# skyrizz_e32_se050.net
KiCad netlist of a schematic drawn in EasyEDA Pro
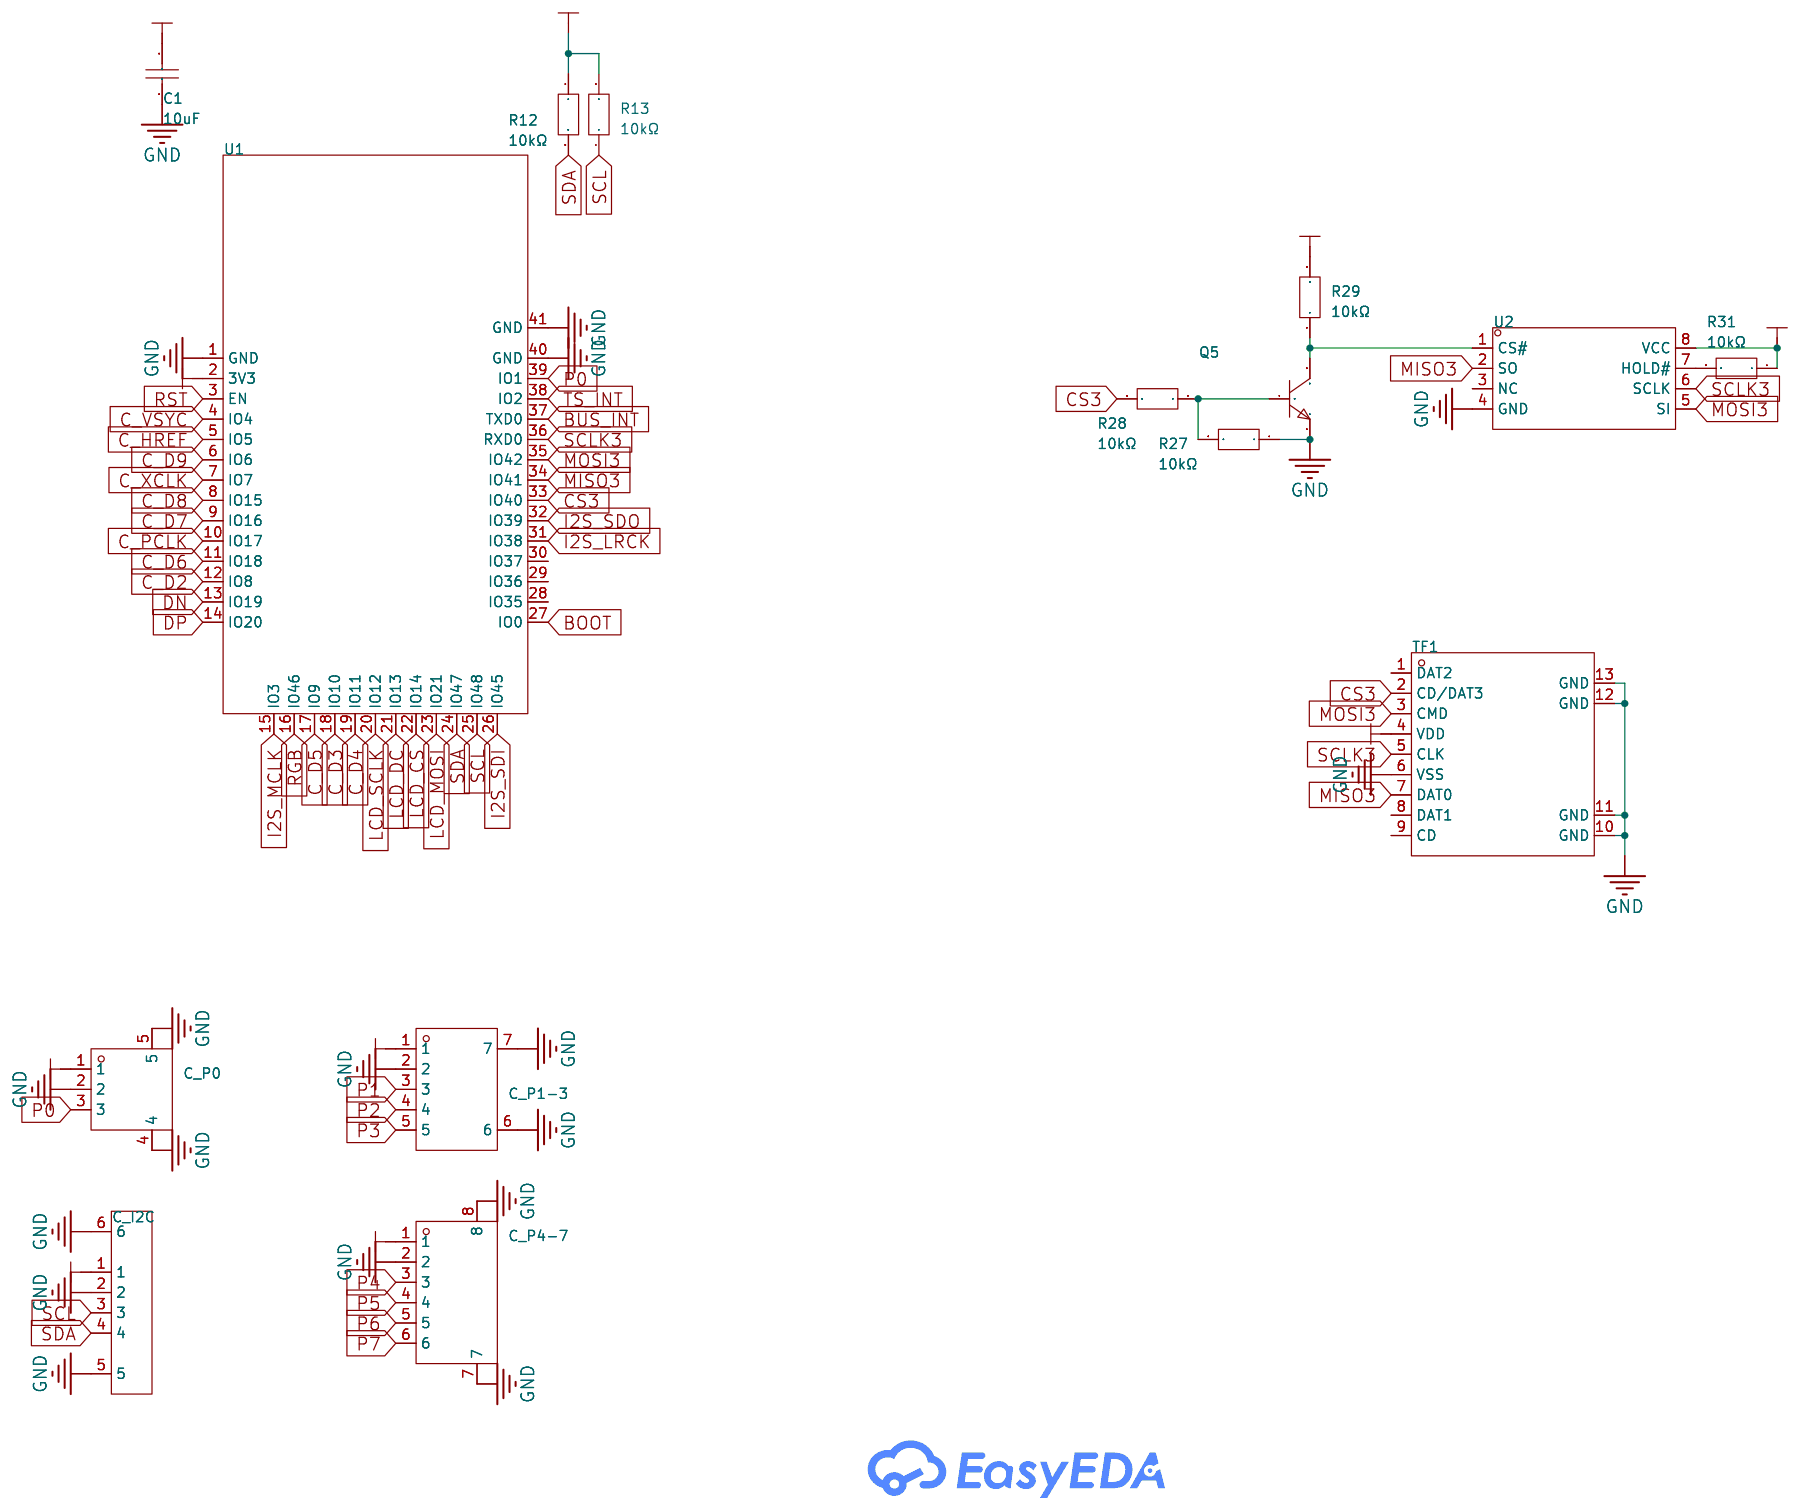
[diagram p0: MCU & MEMORY]
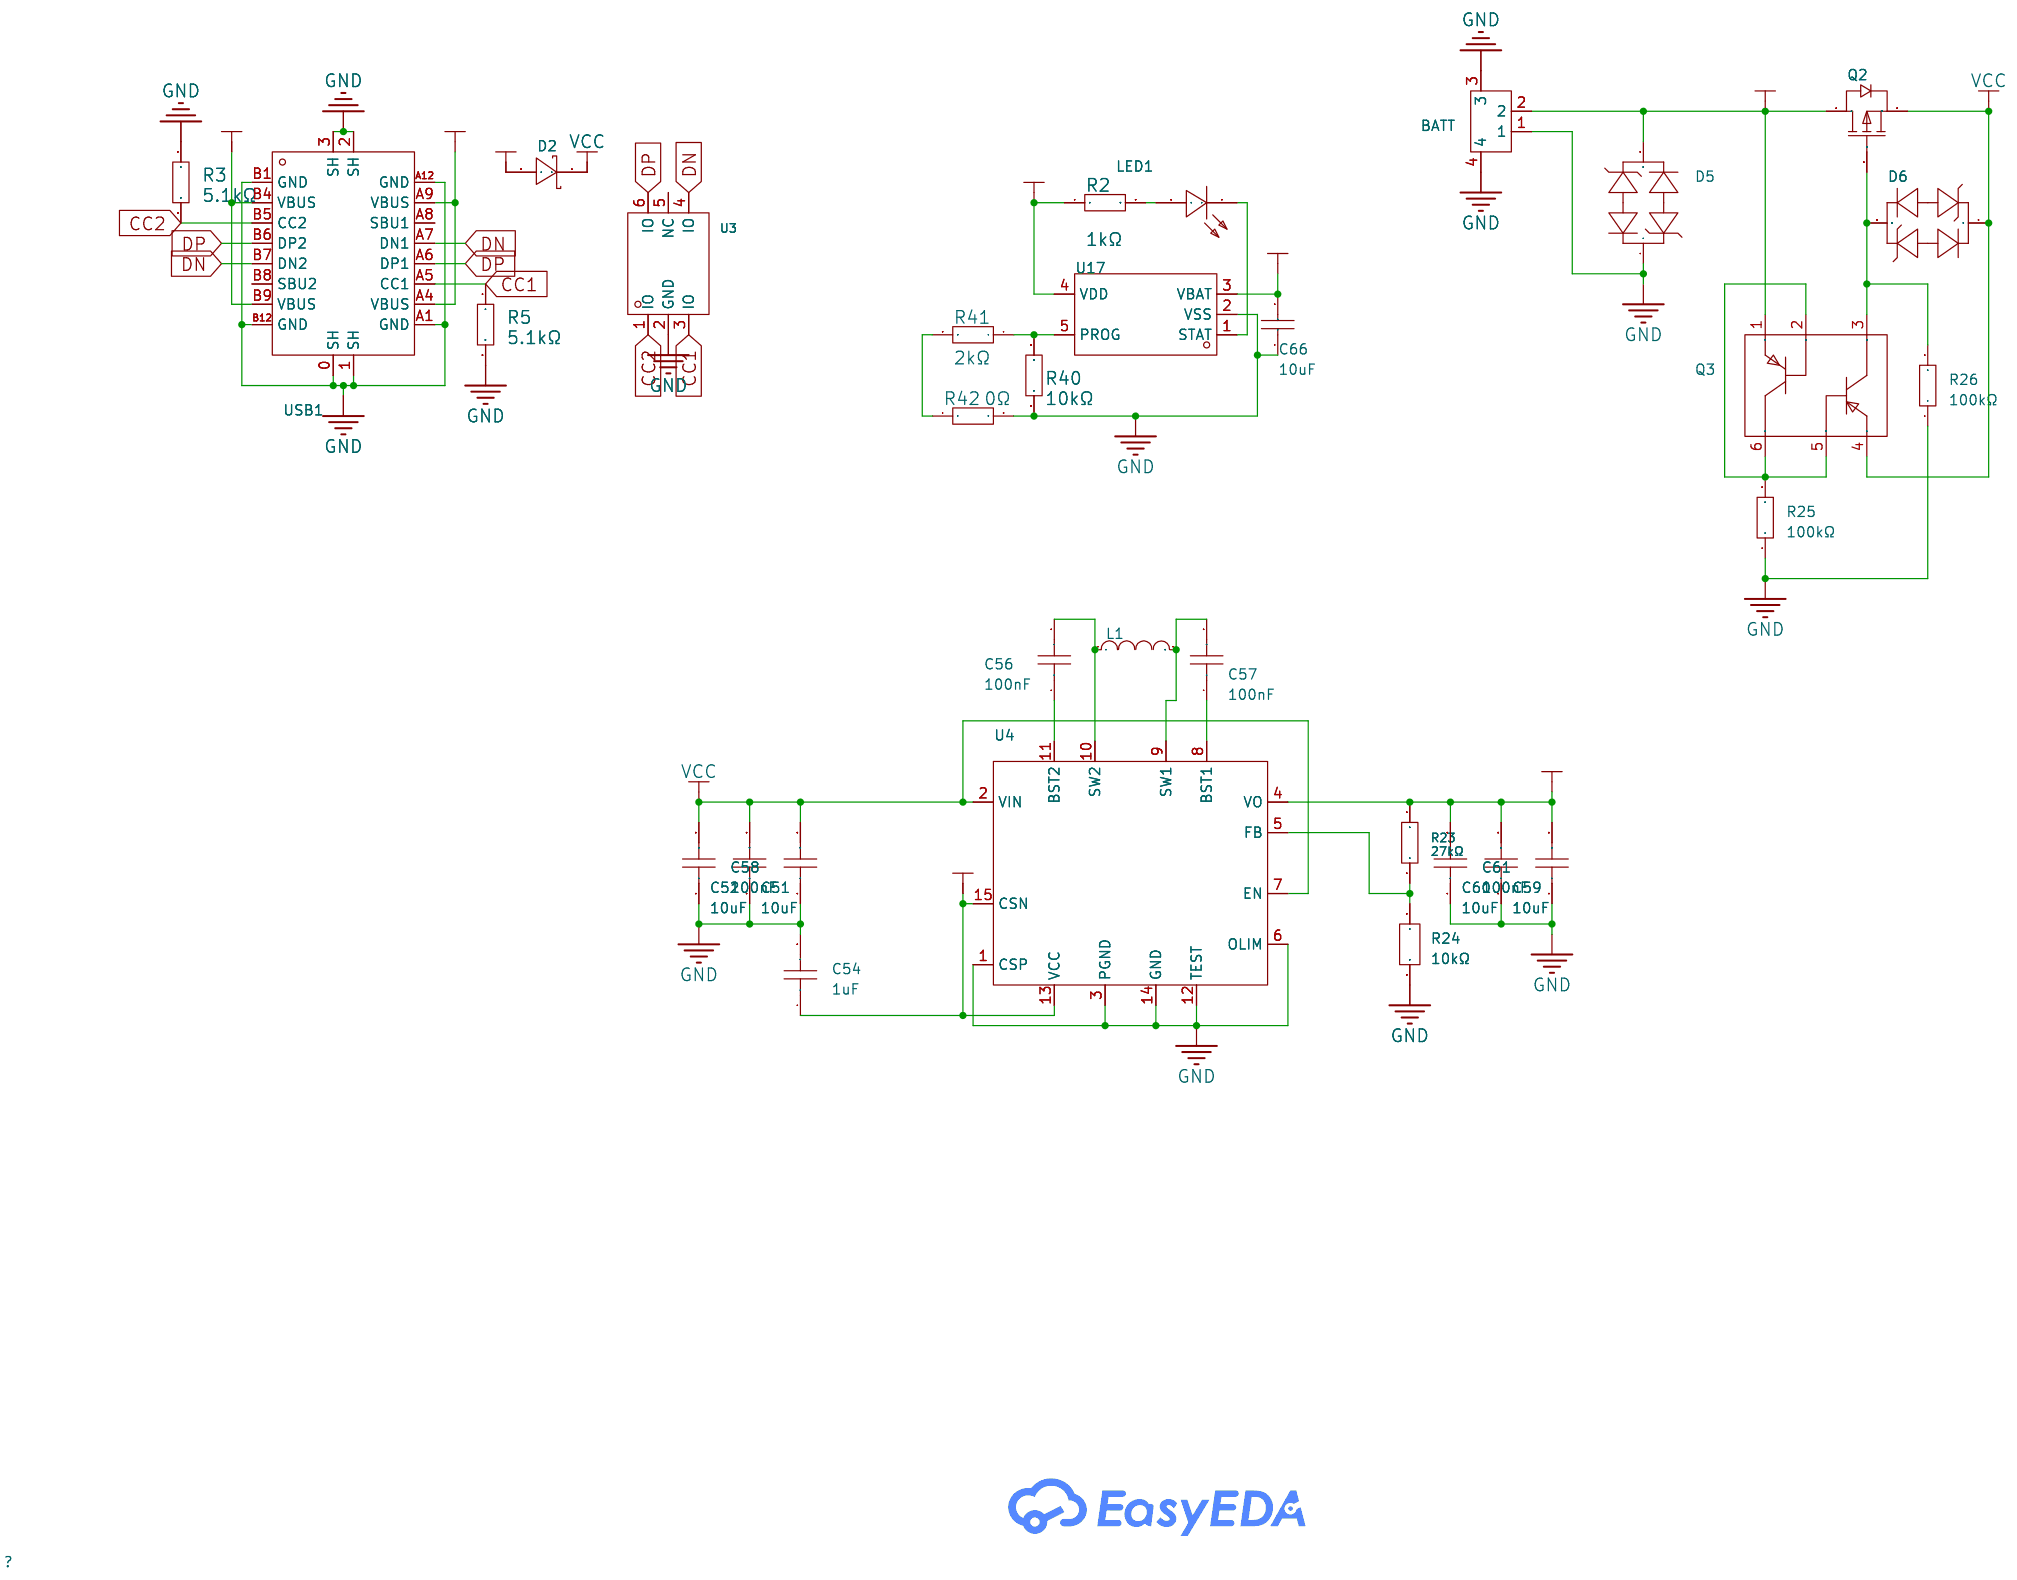
[diagram p1: POWER]
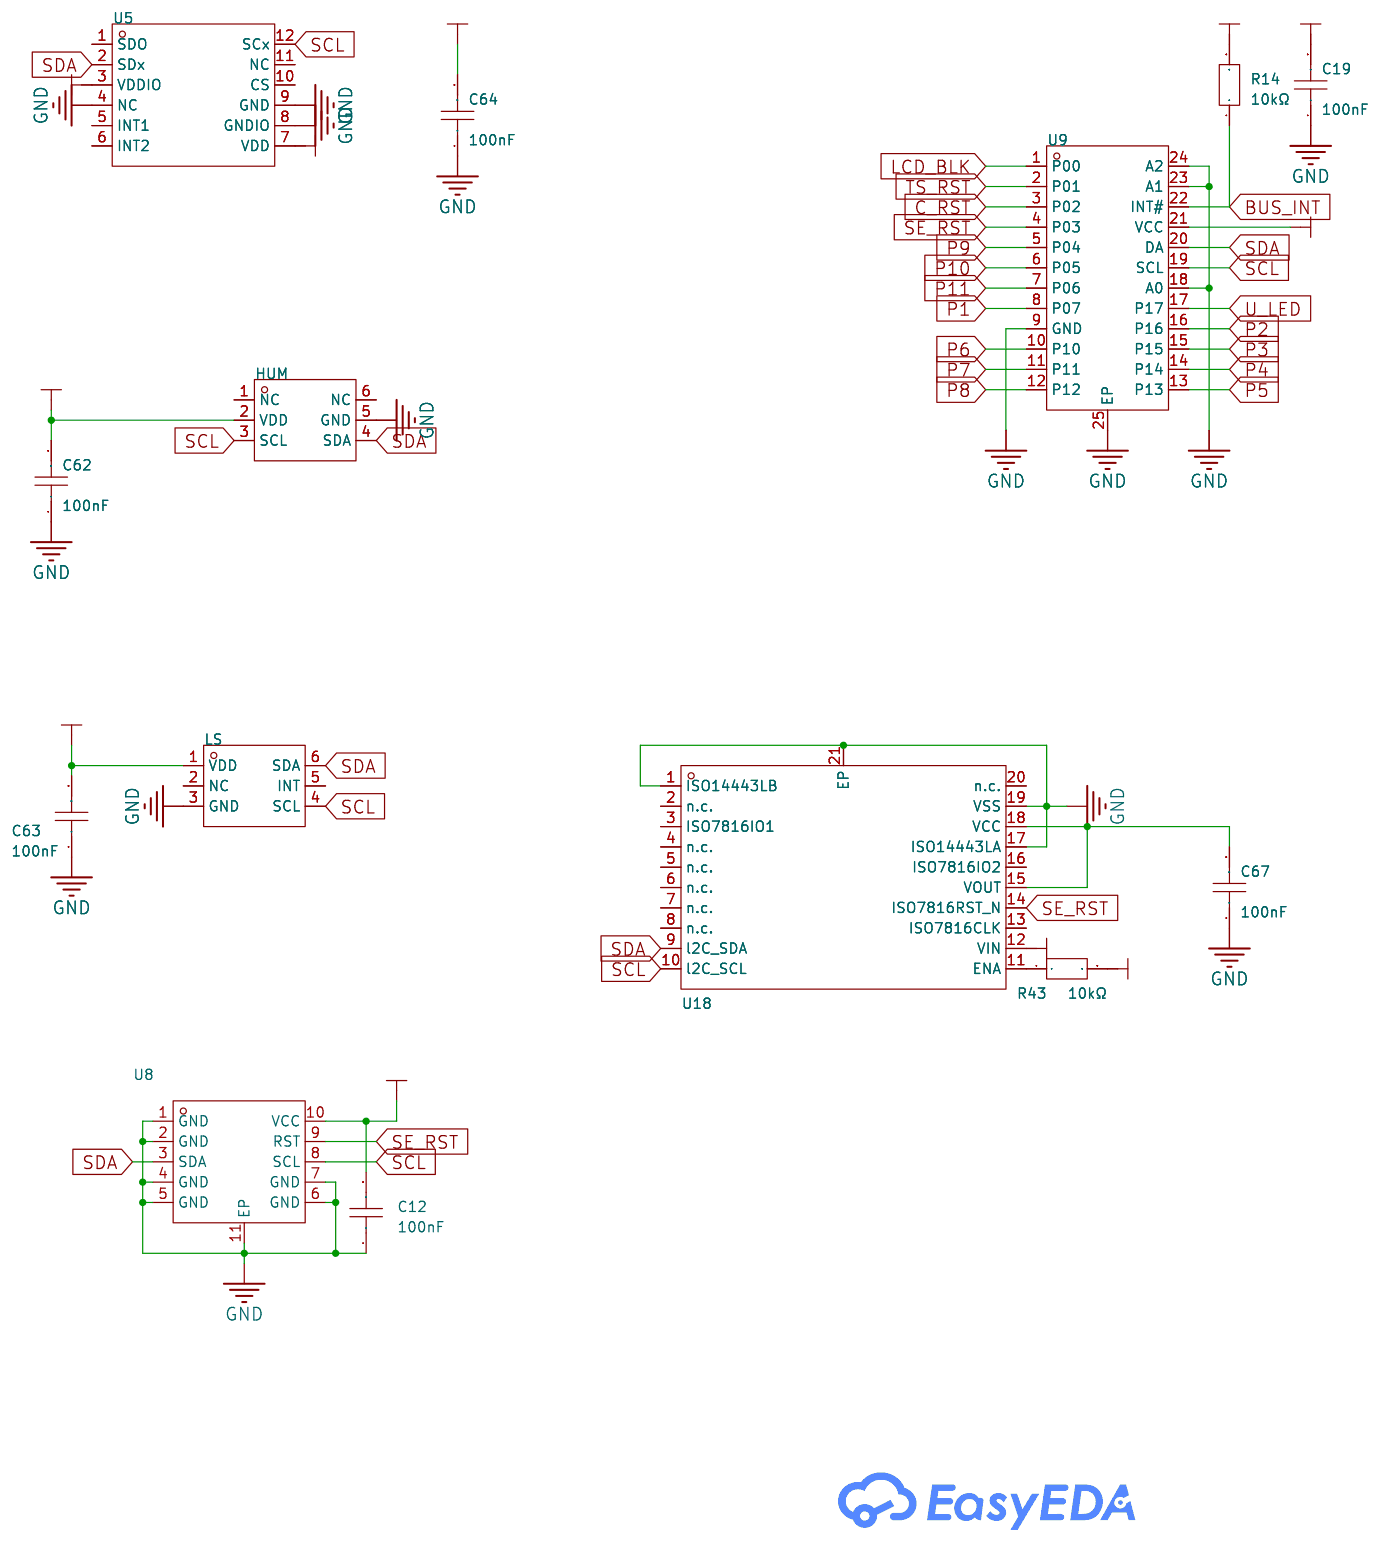
[diagram p2: SENSOR I2C]
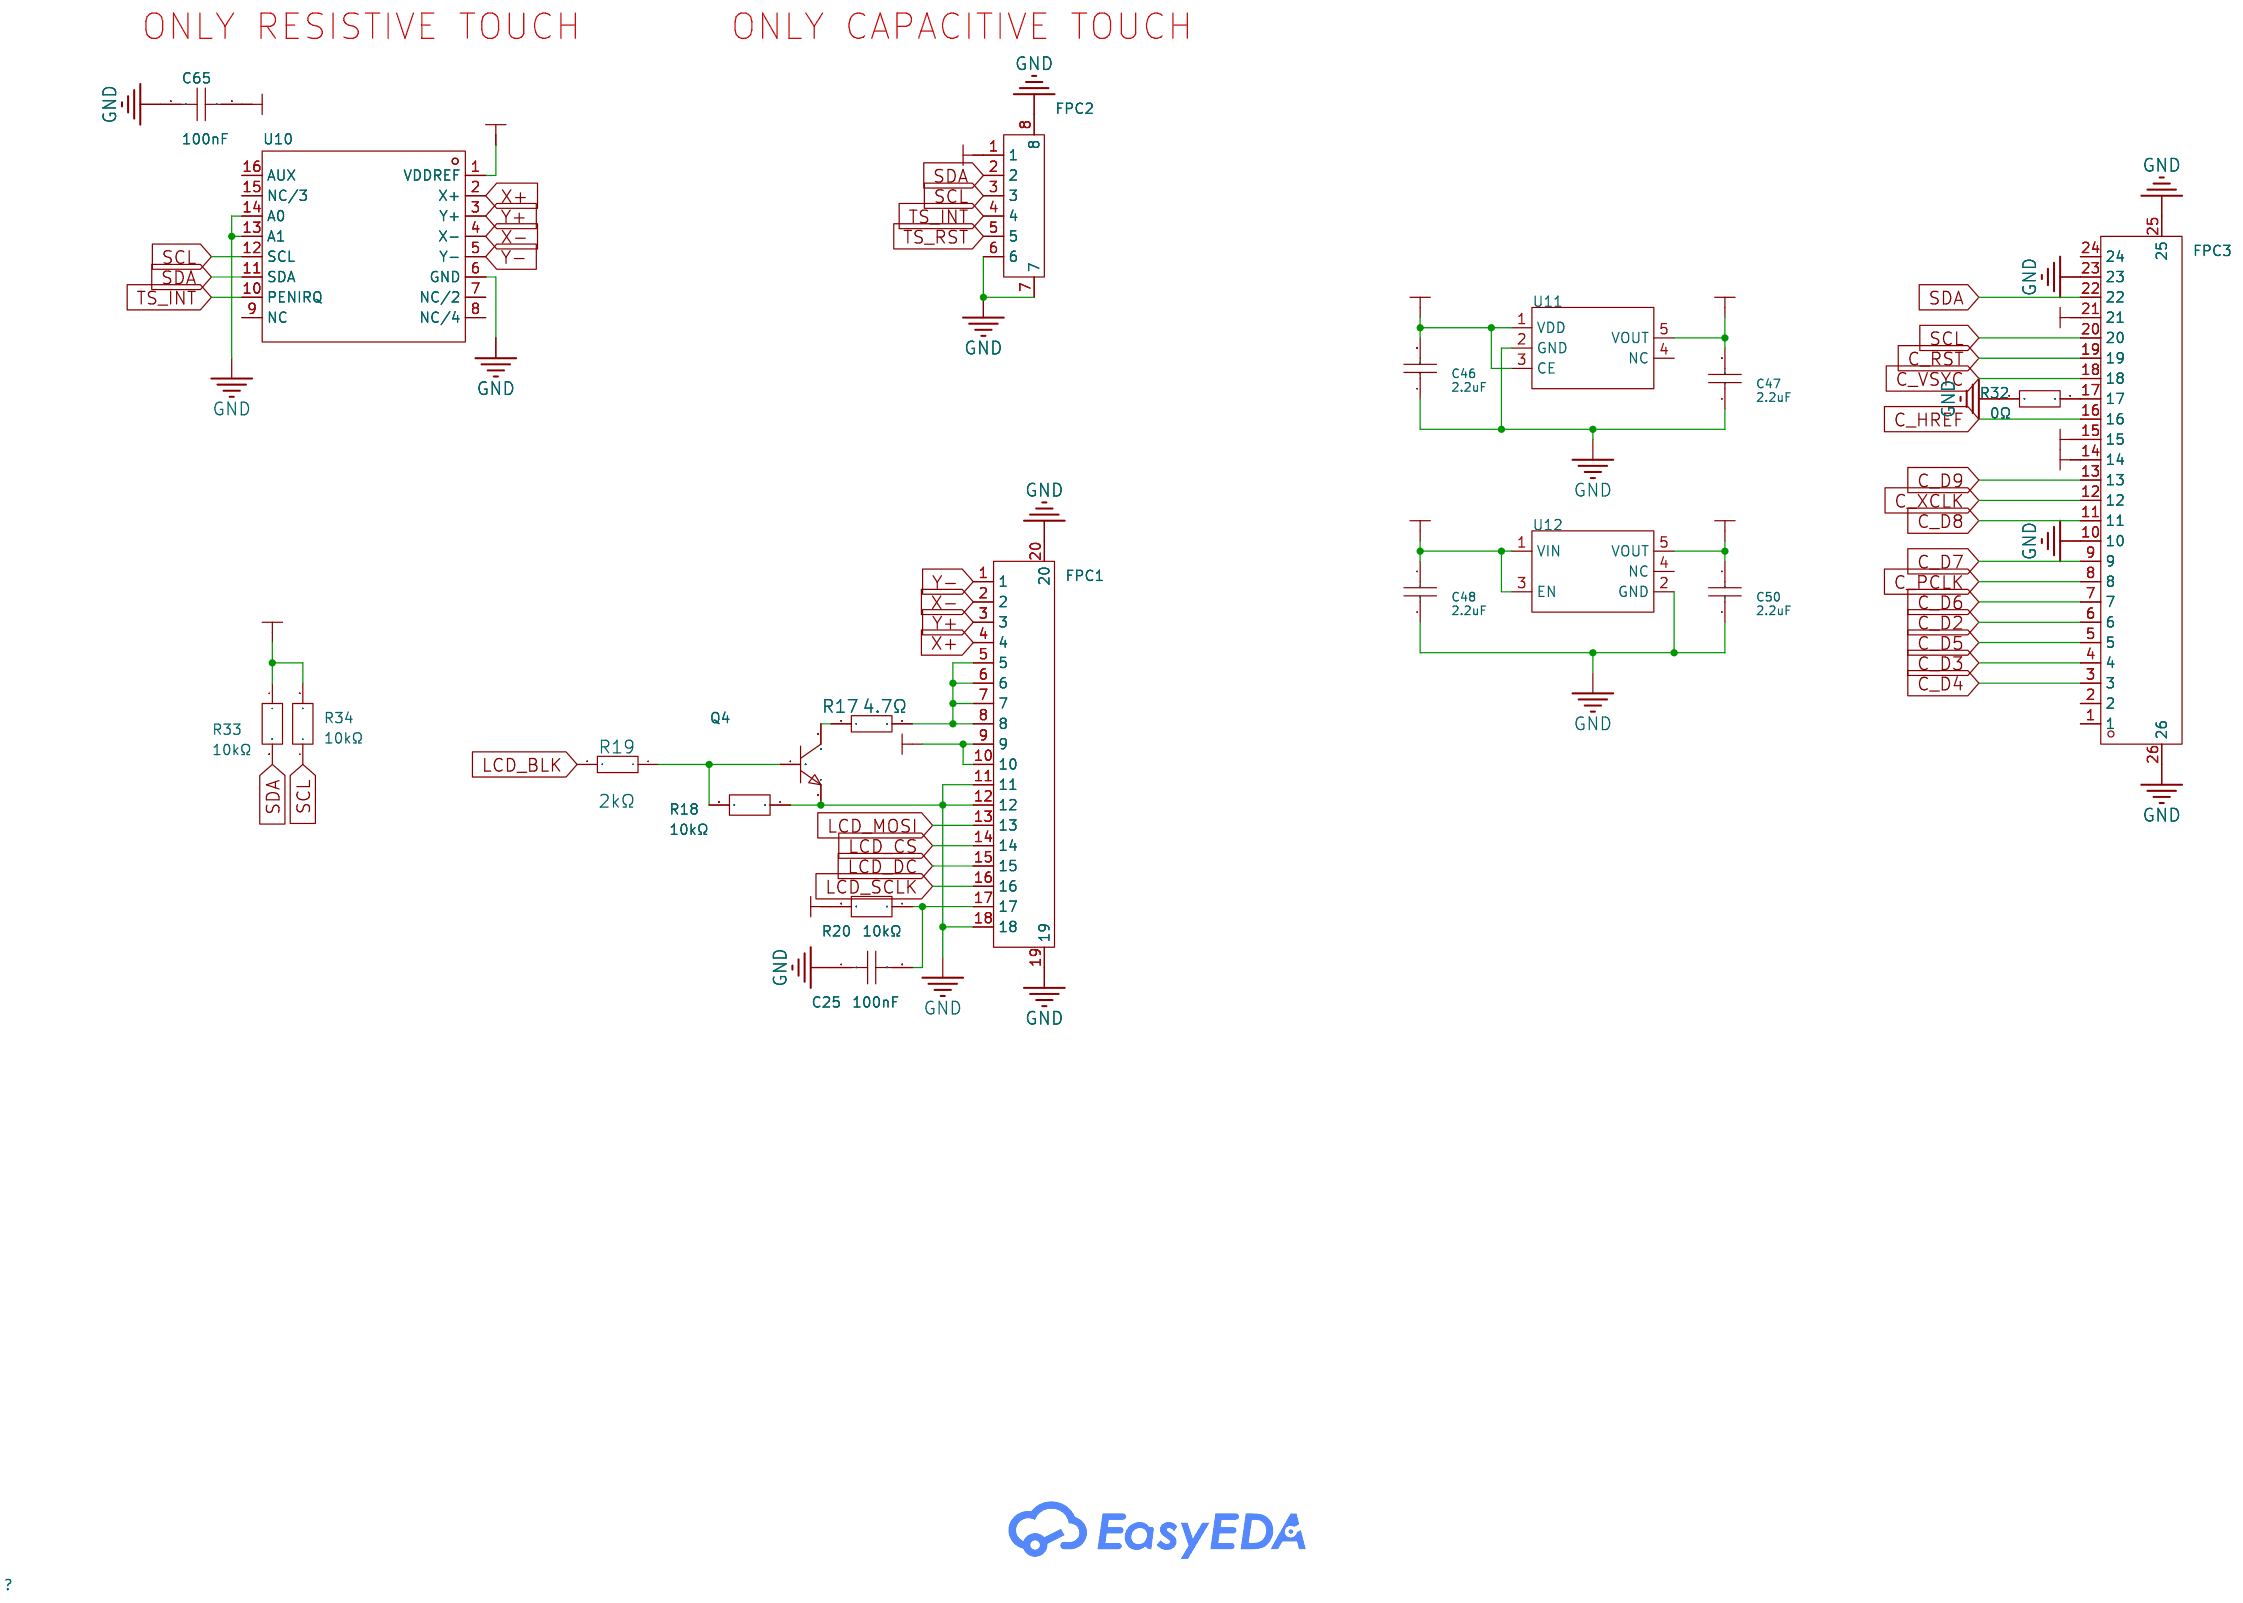
[diagram p3: LCD & CAM]
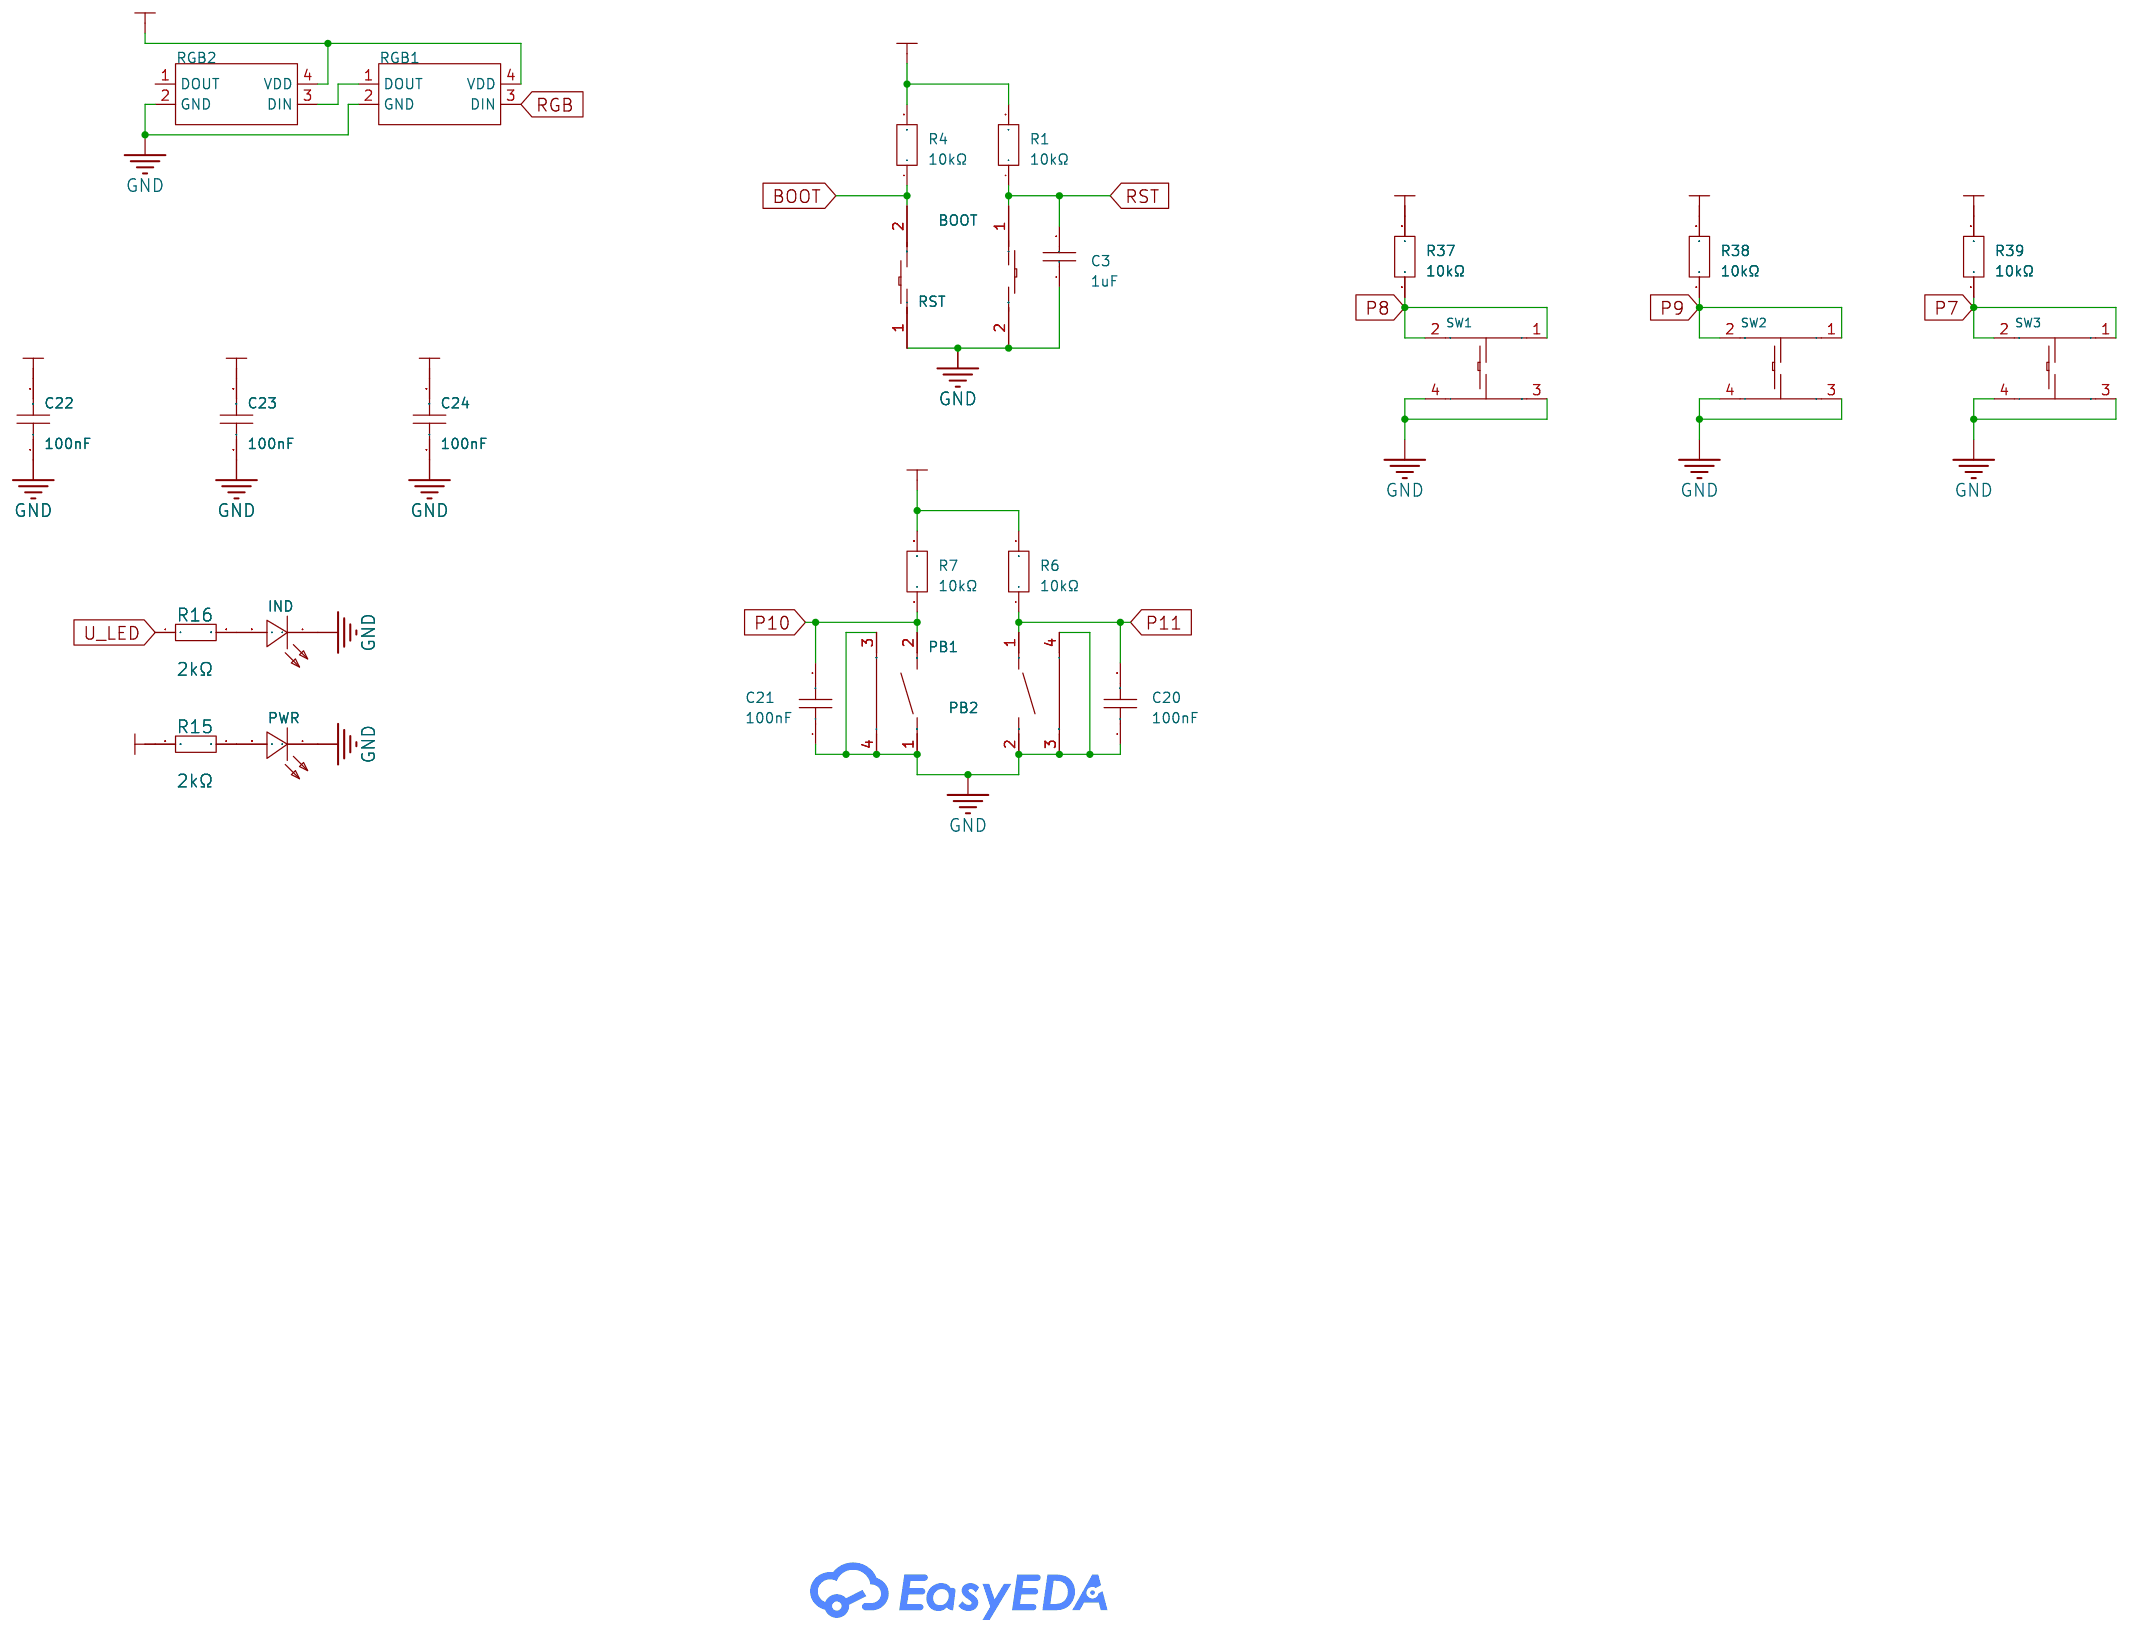
[diagram p4: BUTTON & IND]
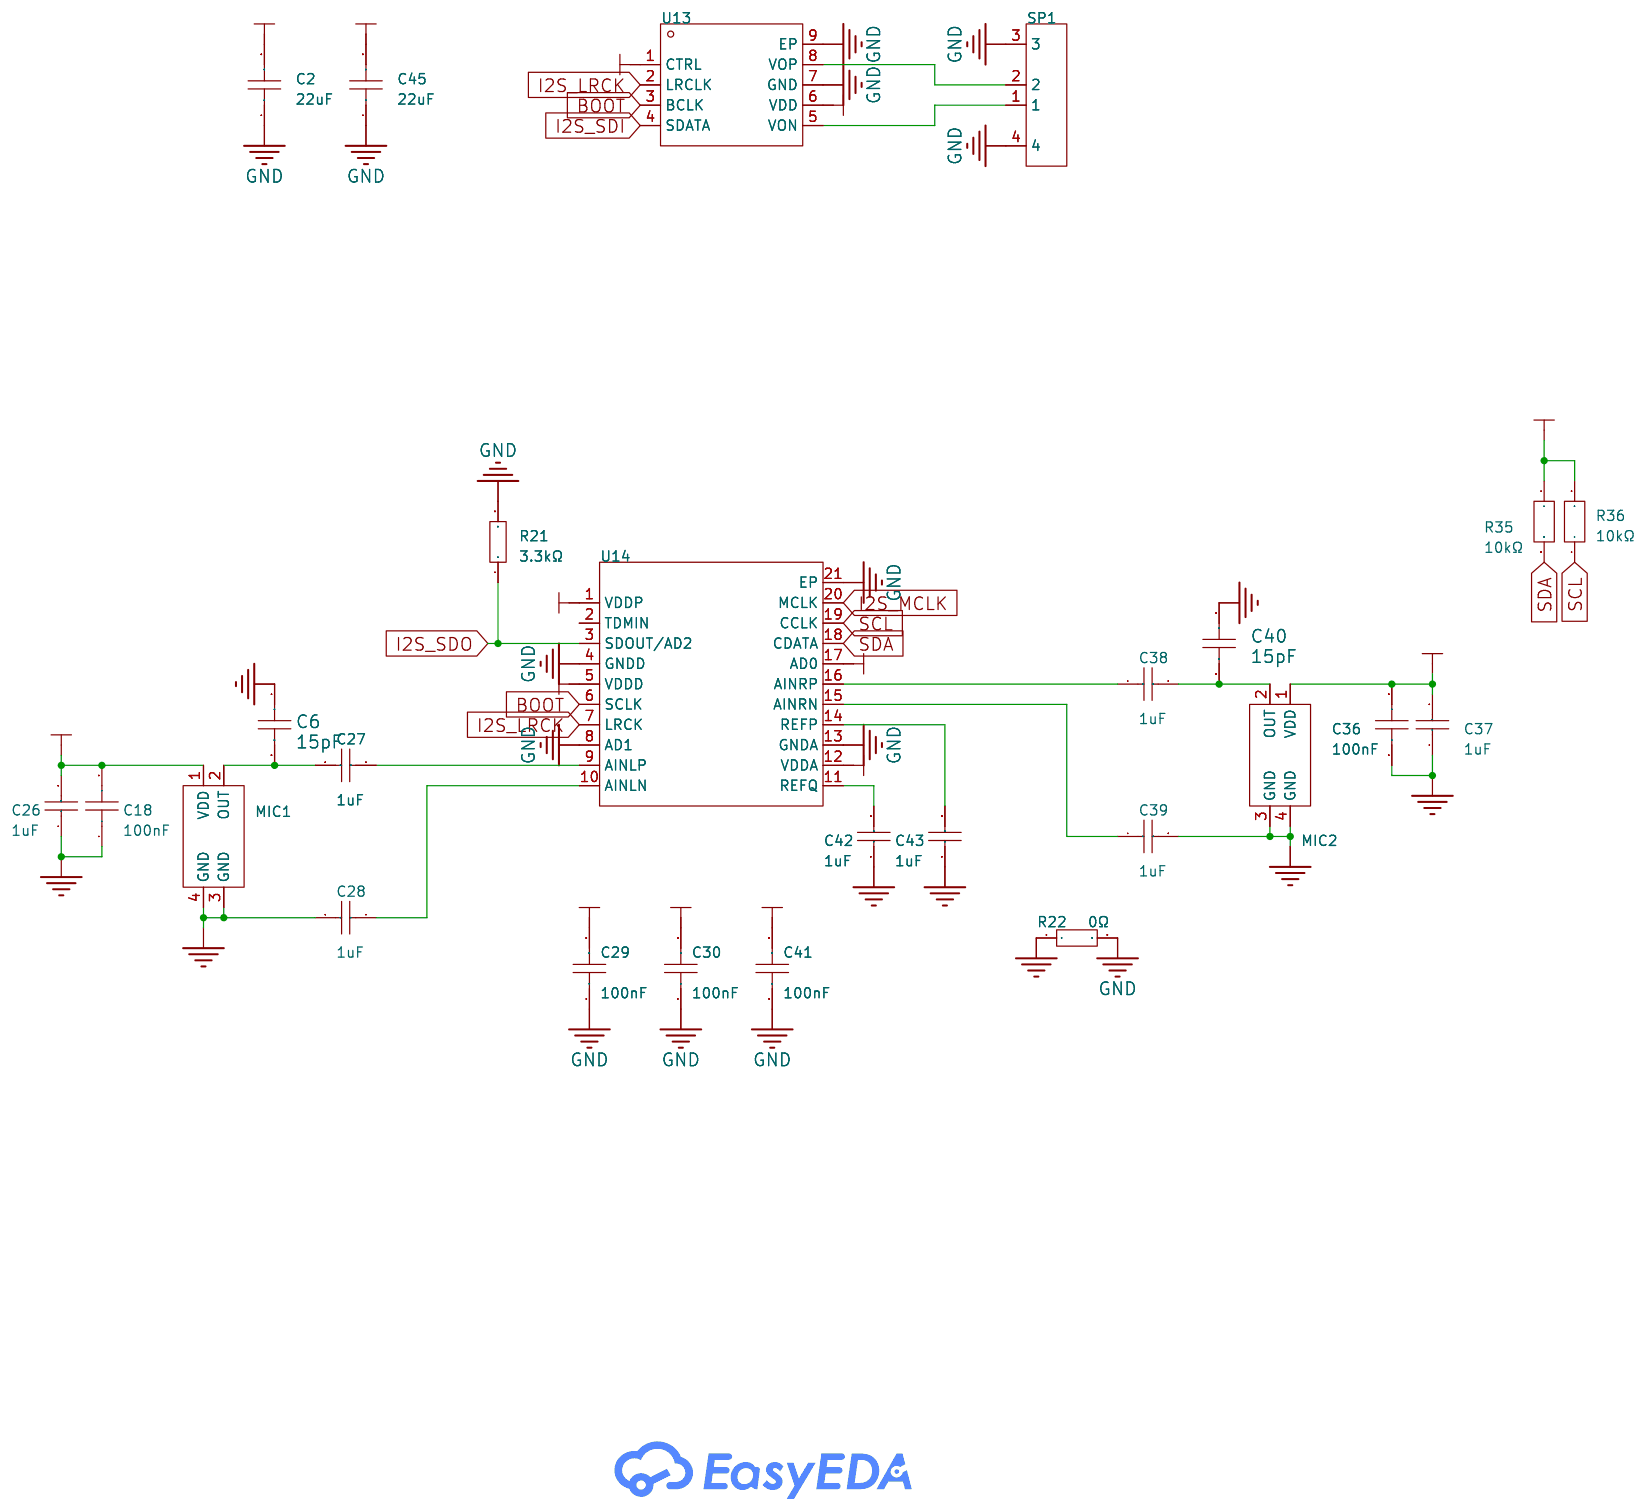
[diagram p5: MIC & SPEAKER]

(export (version "E")
  (design (tool "Eeschema 10.0.6"))
  (components
    (comp (ref "C1")
      (value "10uF")
      (description "Capacitance:10uF Tolerance:±20% Tolerance:±20% Voltage Rating:6.3V Temperature Coefficient:X5R")
      (fields
        (field (name "Manufacturer Part") "CL05A106MQ5NUNC")
        (field (name "Manufacturer") "SAMSUNG(三星)")
      )
      (libsource (lib "easyedapro") (part "CL05A106MQ5NUNC"))
    )
    (comp (ref "C_I2C")
      (value "SM04B-SRSS-TB(LF)(SN)")
      (footprint "easyedapro:CONN-SMD_4P-P1.00_SM04B-SRSS-TB-LF-SN")
      (fields (field (name "Manufacturer") "JST"))
      (libsource (lib "easyedapro") (part "SM04B-SRSS-TB (LF)(SN)"))
    )
    (comp (ref "C_P0")
      (value "SM03B-SRSS-TB(LF)(SN)")
      (footprint "easyedapro:CONN-SMD_SM03B-SRSS-TB-LF-SN-P")
      (fields (field (name "Manufacturer") "JST"))
      (libsource (lib "easyedapro") (part "SM03B-SRSS-TB(LF)(SN)(P)"))
    )
    (comp (ref "C_P1-3")
      (value "SM05B-SRSS-TB(LF)(SN)")
      (footprint "easyedapro:CONN-SMD_SM05B-SRSS-TB-LF-SN")
      (fields (field (name "Manufacturer") "JST"))
      (libsource (lib "easyedapro") (part "SM05B-SRSS-TB (LF)(SN)"))
    )
    (comp (ref "C_P4-7")
      (value "SM06B-SRSS-TB(LF)(SN)")
      (footprint "easyedapro:CONN-SMD_SM06B-SRSS-TB-LF-SN")
      (fields (field (name "Manufacturer") "JST"))
      (libsource (lib "easyedapro") (part "SM06B-SRSS-TB(LF)(SN)"))
    )
    (comp (ref "Q5")
      (value "MMBT3904")
      (footprint "easyedapro:SOT-23-3_L2.9-W1.3-P1.90-LS2.4-BR")
      (fields (field (name "Manufacturer") "DOWO(东沃)"))
      (libsource (lib "easyedapro") (part "MMBT3904_C22374713"))
    )
    (comp (ref "R12")
      (value "10kΩ")
      (footprint "easyedapro:R0201")
      (fields
        (field (name "Manufacturer Part") "0201WMF1002TEE")
        (field (name "Manufacturer") "UNI-ROYAL(厚声)")
      )
      (libsource (lib "easyedapro") (part "0201WMF1002TEE"))
    )
    (comp (ref "R13")
      (value "10kΩ")
      (footprint "easyedapro:R0201")
      (fields
        (field (name "Manufacturer Part") "0201WMF1002TEE")
        (field (name "Manufacturer") "UNI-ROYAL(厚声)")
      )
      (libsource (lib "easyedapro") (part "0201WMF1002TEE"))
    )
    (comp (ref "R27")
      (value "10kΩ")
      (footprint "easyedapro:R0201")
      (fields
        (field (name "Manufacturer Part") "0201WMF1002TEE")
        (field (name "Manufacturer") "UNI-ROYAL(厚声)")
      )
      (libsource (lib "easyedapro") (part "0201WMF1002TEE"))
    )
    (comp (ref "R28")
      (value "10kΩ")
      (footprint "easyedapro:R0201")
      (fields
        (field (name "Manufacturer Part") "0201WMF1002TEE")
        (field (name "Manufacturer") "UNI-ROYAL(厚声)")
      )
      (libsource (lib "easyedapro") (part "0201WMF1002TEE"))
    )
    (comp (ref "R29")
      (value "10kΩ")
      (footprint "easyedapro:R0201")
      (fields
        (field (name "Manufacturer Part") "0201WMF1002TEE")
        (field (name "Manufacturer") "UNI-ROYAL(厚声)")
      )
      (libsource (lib "easyedapro") (part "0201WMF1002TEE"))
    )
    (comp (ref "R31")
      (value "10kΩ")
      (footprint "easyedapro:R0201")
      (fields
        (field (name "Manufacturer Part") "0201WMF1002TEE")
        (field (name "Manufacturer") "UNI-ROYAL(厚声)")
      )
      (libsource (lib "easyedapro") (part "0201WMF1002TEE"))
    )
    (comp (ref "TF1")
      (value "TF-CARD H1.8")
      (footprint "easyedapro:TF-SMD_TF-CARD-H1.8")
      (fields (field (name "Manufacturer") "SHOU HAN(首韩)"))
      (libsource (lib "easyedapro") (part "TF-CARD H1.8"))
    )
    (comp (ref "U1")
      (value "ESP32-S3-WROOM-1-N16R8")
      (footprint "easyedapro:WIRELM-SMD_ESP32-S3-WROOM-1")
      (fields (field (name "Manufacturer") "ESPRESSIF(乐鑫)"))
      (libsource (lib "easyedapro") (part "ESP32-S3-WROOM-1(N16R8)"))
    )
    (comp (ref "U2")
      (value "GT30L24A3W")
      (footprint "easyedapro:SOIC-8_L5.3-W5.3-P1.27-LS8.0-BL")
      (fields (field (name "Manufacturer") "GENITOP(高通)"))
      (libsource (lib "easyedapro") (part "GT30L24A3W"))
    )
    (comp (ref "BATT")
      (value "PH-2P卧贴")
      (footprint "easyedapro:CONN-SMD_2P-P2.00_PH2.0-SPWB")
      (fields (field (name "Manufacturer") "BOOMELE(博穆精密)"))
      (libsource (lib "easyedapro") (part "PH2.0-2PWB"))
    )
    (comp (ref "C51")
      (value "10uF")
      (footprint "easyedapro:C0402")
      (description "Capacitance:10uF Tolerance:±20% Tolerance:±20% Voltage Rating:10V Temperature Coefficient:X5R")
      (fields
        (field (name "Manufacturer Part") "GRM155R61A106ME44D")
        (field (name "Manufacturer") "muRata(村田)")
      )
      (libsource (lib "easyedapro") (part "GRM155R61A106ME44D"))
    )
    (comp (ref "C52")
      (value "10uF")
      (footprint "easyedapro:C0402")
      (description "Capacitance:10uF Tolerance:±20% Tolerance:±20% Voltage Rating:10V Temperature Coefficient:X5R")
      (fields
        (field (name "Manufacturer Part") "GRM155R61A106ME44D")
        (field (name "Manufacturer") "muRata(村田)")
      )
      (libsource (lib "easyedapro") (part "GRM155R61A106ME44D"))
    )
    (comp (ref "C54")
      (value "1uF")
      (footprint "easyedapro:C0402")
      (description "Capacitance:1uF Tolerance:±10% Tolerance:±10% Voltage Rating:25V Temperature Coefficient:X5R")
      (fields
        (field (name "Manufacturer Part") "CL05A105KA5NQNC")
        (field (name "Manufacturer") "SAMSUNG(三星)")
      )
      (libsource (lib "easyedapro") (part "CL05A105KA5NQNC"))
    )
    (comp (ref "C56")
      (value "100nF")
      (footprint "easyedapro:C0402")
      (description "Capacitance:100nF Tolerance:±10% Tolerance:±10% Voltage Rating:16V Temperature Coefficient:X7R")
      (fields
        (field (name "Manufacturer Part") "CL05B104KO5NNNC")
        (field (name "Manufacturer") "SAMSUNG(三星)")
      )
      (libsource (lib "easyedapro") (part "CL05B104KO5NNNC"))
    )
    (comp (ref "C57")
      (value "100nF")
      (footprint "easyedapro:C0402")
      (description "Capacitance:100nF Tolerance:±10% Tolerance:±10% Voltage Rating:16V Temperature Coefficient:X7R")
      (fields
        (field (name "Manufacturer Part") "CL05B104KO5NNNC")
        (field (name "Manufacturer") "SAMSUNG(三星)")
      )
      (libsource (lib "easyedapro") (part "CL05B104KO5NNNC"))
    )
    (comp (ref "C58")
      (value "100nF")
      (footprint "easyedapro:C0402")
      (description "Capacitance:100nF Tolerance:±10% Tolerance:±10% Voltage Rating:16V Temperature Coefficient:X7R")
      (fields
        (field (name "Manufacturer Part") "CL05B104KO5NNNC")
        (field (name "Manufacturer") "SAMSUNG(三星)")
      )
      (libsource (lib "easyedapro") (part "CL05B104KO5NNNC"))
    )
    (comp (ref "C59")
      (value "10uF")
      (footprint "easyedapro:C0402")
      (description "Capacitance:10uF Tolerance:±20% Tolerance:±20% Voltage Rating:10V Temperature Coefficient:X5R")
      (fields
        (field (name "Manufacturer Part") "GRM155R61A106ME44D")
        (field (name "Manufacturer") "muRata(村田)")
      )
      (libsource (lib "easyedapro") (part "GRM155R61A106ME44D"))
    )
    (comp (ref "C60")
      (value "10uF")
      (footprint "easyedapro:C0402")
      (description "Capacitance:10uF Tolerance:±20% Tolerance:±20% Voltage Rating:10V Temperature Coefficient:X5R")
      (fields
        (field (name "Manufacturer Part") "GRM155R61A106ME44D")
        (field (name "Manufacturer") "muRata(村田)")
      )
      (libsource (lib "easyedapro") (part "GRM155R61A106ME44D"))
    )
    (comp (ref "C61")
      (value "100nF")
      (footprint "easyedapro:C0402")
      (description "Capacitance:100nF Tolerance:±10% Tolerance:±10% Voltage Rating:16V Temperature Coefficient:X7R")
      (fields
        (field (name "Manufacturer Part") "CL05B104KO5NNNC")
        (field (name "Manufacturer") "SAMSUNG(三星)")
      )
      (libsource (lib "easyedapro") (part "CL05B104KO5NNNC"))
    )
    (comp (ref "C66")
      (value "10uF")
      (description "Capacitance:10uF Tolerance:±20% Tolerance:±20% Voltage Rating:6.3V Temperature Coefficient:X5R")
      (fields
        (field (name "Manufacturer Part") "CL05A106MQ5NUNC")
        (field (name "Manufacturer") "SAMSUNG(三星)")
      )
      (libsource (lib "easyedapro") (part "CL05A106MQ5NUNC"))
    )
    (comp (ref "D2")
      (value "SS34")
      (footprint "easyedapro:SMA_L4.3-W2.6-LS5.2-RD")
      (fields (field (name "Manufacturer") "MDD(辰达半导体)"))
      (libsource (lib "easyedapro") (part "SS34_C8678"))
    )
    (comp (ref "D5")
      (value "PTVSUC3D5VB")
      (footprint "easyedapro:SOD-323_L1.8-W1.3-LS2.5-BI")
      (fields (field (name "Manufacturer") "Prisemi(芯导)"))
      (libsource (lib "easyedapro") (part "PTVSUC3D5VB"))
    )
    (comp (ref "D6")
      (value "PTVSUC3D5VB")
      (footprint "easyedapro:SOD-323_L1.8-W1.3-LS2.5-BI")
      (fields (field (name "Manufacturer") "Prisemi(芯导)"))
      (libsource (lib "easyedapro") (part "PTVSUC3D5VB"))
    )
    (comp (ref "L1")
      (value "2.2uH")
      (footprint "easyedapro:IND-SMD_L3.5-W3.0")
      (fields (field (name "Manufacturer Part") "SM3521-2R2MT") (field (name "Manufacturer") "SXN(顺翔诺)"))
      (libsource (lib "easyedapro") (part "SM3521-2R2MT"))
    )
    (comp (ref "LED1")
      (value "KT-0603R")
      (fields (field (name "Manufacturer") "KENTO"))
      (libsource (lib "easyedapro") (part "KT-0603R"))
    )
    (comp (ref "Q2")
      (value "AO3401A")
      (fields (field (name "Manufacturer") "AOS"))
      (libsource (lib "easyedapro") (part "AO3401A"))
    )
    (comp (ref "Q3")
      (value "BCM857BS")
      (footprint "easyedapro:SOT-363_L2.1-W1.3-P0.65-LS2.3-BL")
      (fields (field (name "Manufacturer") "FUXINSEMI(富芯森美)"))
      (libsource (lib "easyedapro") (part "BCM857BS"))
    )
    (comp (ref "R2")
      (value "1kΩ")
      (footprint "easyedapro:R0201")
      (fields
        (field (name "Manufacturer Part") "0201WMF1001TEE")
        (field (name "Manufacturer") "UNI-ROYAL(厚声)")
      )
      (libsource (lib "easyedapro") (part "0201WMF1001TEE"))
    )
    (comp (ref "R3")
      (value "5.1kΩ")
      (footprint "easyedapro:R0201")
      (fields
        (field (name "Manufacturer Part") "0201WMF5101TEE")
        (field (name "Manufacturer") "UNI-ROYAL(厚声)")
      )
      (libsource (lib "easyedapro") (part "0201WMF5101TEE"))
    )
    (comp (ref "R5")
      (value "5.1kΩ")
      (footprint "easyedapro:R0201")
      (fields
        (field (name "Manufacturer Part") "0201WMF5101TEE")
        (field (name "Manufacturer") "UNI-ROYAL(厚声)")
      )
      (libsource (lib "easyedapro") (part "0201WMF5101TEE"))
    )
    (comp (ref "R23")
      (value "27kΩ")
      (footprint "easyedapro:R0201")
      (fields
        (field (name "Manufacturer Part") "0201WMF2702TEE")
        (field (name "Manufacturer") "UNI-ROYAL(厚声)")
      )
      (libsource (lib "easyedapro") (part "0201WMF2702TEE"))
    )
    (comp (ref "R24")
      (value "10kΩ")
      (footprint "easyedapro:R0201")
      (fields
        (field (name "Manufacturer Part") "0201WMF1002TEE")
        (field (name "Manufacturer") "UNI-ROYAL(厚声)")
      )
      (libsource (lib "easyedapro") (part "0201WMF1002TEE"))
    )
    (comp (ref "R25")
      (value "100kΩ")
      (footprint "easyedapro:R0201")
      (fields
        (field (name "Manufacturer Part") "0201WMF1003TEE")
        (field (name "Manufacturer") "UNI-ROYAL(厚声)")
      )
      (libsource (lib "easyedapro") (part "0201WMF1003TEE"))
    )
    (comp (ref "R26")
      (value "100kΩ")
      (footprint "easyedapro:R0201")
      (fields
        (field (name "Manufacturer Part") "0201WMF1003TEE")
        (field (name "Manufacturer") "UNI-ROYAL(厚声)")
      )
      (libsource (lib "easyedapro") (part "0201WMF1003TEE"))
    )
    (comp (ref "R40")
      (value "10kΩ")
      (footprint "easyedapro:R0201")
      (fields
        (field (name "Manufacturer Part") "0201WMF1002TEE")
        (field (name "Manufacturer") "UNI-ROYAL(厚声)")
      )
      (libsource (lib "easyedapro") (part "0201WMF1001TEE"))
    )
    (comp (ref "R41")
      (value "2kΩ")
      (footprint "easyedapro:R0201")
      (fields
        (field (name "Manufacturer Part") "0201WMF2001TEE")
        (field (name "Manufacturer") "UNI-ROYAL(厚声)")
      )
      (libsource (lib "easyedapro") (part "0201WMF1001TEE"))
    )
    (comp (ref "R42")
      (value "0Ω")
      (footprint "easyedapro:R0402")
      (fields
        (field (name "Manufacturer Part") "0402WGF0000TCE")
        (field (name "Manufacturer") "UNI-ROYAL(厚声)")
      )
      (libsource (lib "easyedapro") (part "0402WGF0000TCE"))
    )
    (comp (ref "U3")
      (value "PUSB2X4Y")
      (footprint "easyedapro:SOT-363-6_L2.0-W1.3-P0.65-LS2.1-BL")
      (fields (field (name "Manufacturer") "TECH PUBLIC(台舟)"))
      (libsource (lib "easyedapro") (part "PUSB2X4Y"))
    )
    (comp (ref "U4")
      (value "JW3651QFNE#TRPBF")
      (footprint "easyedapro:QFN-15_L4.0-W3.0_JW3655E")
      (fields (field (name "Manufacturer") "Joulwatt(杰华特)"))
      (libsource (lib "easyedapro") (part "JW3651QFNE#TRPBF"))
    )
    (comp (ref "U17")
      (value "MCP73831T-2ACI/OT")
      (footprint "easyedapro:SOT-23-5_L3.0-W1.7-P0.95-LS2.8-BL")
      (fields (field (name "Manufacturer") "MICROCHIP(美国微芯)"))
      (libsource (lib "easyedapro") (part "MCP73831T-2ACI/OT"))
    )
    (comp (ref "USB1")
      (value "USB-TYPE-C-018")
      (footprint "easyedapro:USB-C_SMD-TYPE-C-31-M-12")
      (fields (field (name "Manufacturer") "DEALON(德艺隆)"))
      (libsource (lib "easyedapro") (part "USB-TYPE-C-018"))
    )
    (comp (ref "C12")
      (value "100nF")
      (footprint "easyedapro:C0201")
      (description "Capacitance:100nF Tolerance:±10% Tolerance:±10% Voltage Rating:10V Temperature Coefficient:X5R")
      (fields
        (field (name "Manufacturer Part") "CL03A104KP3NNNC")
        (field (name "Manufacturer") "SAMSUNG(三星)")
      )
      (libsource (lib "easyedapro") (part "CL03A104KP3NNNC"))
    )
    (comp (ref "C19")
      (value "100nF")
      (footprint "easyedapro:C0201")
      (description "Capacitance:100nF Tolerance:±10% Tolerance:±10% Voltage Rating:10V Temperature Coefficient:X5R")
      (fields
        (field (name "Manufacturer Part") "CL03A104KP3NNNC")
        (field (name "Manufacturer") "SAMSUNG(三星)")
      )
      (libsource (lib "easyedapro") (part "CL03A104KP3NNNC"))
    )
    (comp (ref "C62")
      (value "100nF")
      (footprint "easyedapro:C0201")
      (description "Capacitance:100nF Tolerance:±10% Tolerance:±10% Voltage Rating:10V Temperature Coefficient:X5R")
      (fields
        (field (name "Manufacturer Part") "CL03A104KP3NNNC")
        (field (name "Manufacturer") "SAMSUNG(三星)")
      )
      (libsource (lib "easyedapro") (part "CL03A104KP3NNNC"))
    )
    (comp (ref "C63")
      (value "100nF")
      (footprint "easyedapro:C0201")
      (description "Capacitance:100nF Tolerance:±10% Tolerance:±10% Voltage Rating:10V Temperature Coefficient:X5R")
      (fields
        (field (name "Manufacturer Part") "CL03A104KP3NNNC")
        (field (name "Manufacturer") "SAMSUNG(三星)")
      )
      (libsource (lib "easyedapro") (part "CL03A104KP3NNNC"))
    )
    (comp (ref "C64")
      (value "100nF")
      (footprint "easyedapro:C0201")
      (description "Capacitance:100nF Tolerance:±10% Tolerance:±10% Voltage Rating:10V Temperature Coefficient:X5R")
      (fields
        (field (name "Manufacturer Part") "CL03A104KP3NNNC")
        (field (name "Manufacturer") "SAMSUNG(三星)")
      )
      (libsource (lib "easyedapro") (part "CL03A104KP3NNNC"))
    )
    (comp (ref "C67")
      (value "100nF")
      (footprint "easyedapro:C0201")
      (description "Capacitance:100nF Tolerance:±10% Tolerance:±10% Voltage Rating:10V Temperature Coefficient:X5R")
      (fields
        (field (name "Manufacturer Part") "CL03A104KP3NNNC")
        (field (name "Manufacturer") "SAMSUNG(三星)")
      )
      (libsource (lib "easyedapro") (part "CL03A104KP3NNNC"))
    )
    (comp (ref "HUM")
      (value "AHT20")
      (footprint "easyedapro:SENSOR-SMD_L3.0-W3.0-P1.00-BR")
      (fields (field (name "Manufacturer") "广州奥松"))
      (libsource (lib "easyedapro") (part "AHT20_C2757850"))
    )
    (comp (ref "LS")
      (value "LTR-303ALS-01")
      (footprint "easyedapro:TDFN-6_L2.0-W2.0-P0.65-BL")
      (fields (field (name "Manufacturer") "LITEON(光宝)"))
      (libsource (lib "easyedapro") (part "LTR-303ALS-01"))
    )
    (comp (ref "R14")
      (value "10kΩ")
      (footprint "easyedapro:R0201")
      (fields
        (field (name "Manufacturer Part") "0201WMF1002TEE")
        (field (name "Manufacturer") "UNI-ROYAL(厚声)")
      )
      (libsource (lib "easyedapro") (part "0201WMF1002TEE"))
    )
    (comp (ref "R43")
      (value "10kΩ")
      (footprint "easyedapro:R0201")
      (fields
        (field (name "Manufacturer Part") "0201WMF1002TEE")
        (field (name "Manufacturer") "UNI-ROYAL(厚声)")
      )
      (libsource (lib "easyedapro") (part "0201WMF1002TEE"))
    )
    (comp (ref "U5")
      (value "SC7A20HTR")
      (footprint "easyedapro:LGA-12_L2.0-W2.0-P0.50-TL")
      (fields (field (name "Manufacturer") "SILAN(士兰微)"))
      (libsource (lib "easyedapro") (part "SC7A20HTR"))
    )
    (comp (ref "U8")
      (value "SLS32AIA020X2USON10")
      (footprint "easyedapro:USON-10_L3.0-W3.0-P0.50-BL-EP")
      (fields (field (name "Manufacturer") "Infineon(英飞凌)"))
      (libsource (lib "easyedapro") (part "SLS32AIA020X2USON10XTMA4"))
    )
    (comp (ref "U9")
      (value "XL9535QF24")
      (footprint "easyedapro:QFN-24_L4.0-W4.0-P0.50-BL-EP2.6")
      (fields (field (name "Manufacturer") "XINLUDA(信路达)"))
      (libsource (lib "easyedapro") (part "XL9535QF24"))
    )
    (comp (ref "U18")
      (value "SE050C2HQ1/Z01SDZ")
      (footprint "easyedapro:WQFN-20_L3.0-W3.0-P0.40-BL-EP1.7")
      (fields (field (name "Manufacturer") "NXP(恩智浦)"))
      (libsource (lib "easyedapro") (part "SE050C2HQ1/Z01SDZ"))
    )
    (comp (ref "C25")
      (value "100nF")
      (footprint "easyedapro:C0201")
      (description "Capacitance:100nF Tolerance:±10% Tolerance:±10% Voltage Rating:10V Temperature Coefficient:X5R")
      (fields
        (field (name "Manufacturer Part") "CL03A104KP3NNNC")
        (field (name "Manufacturer") "SAMSUNG(三星)")
      )
      (libsource (lib "easyedapro") (part "CL03A104KP3NNNC"))
    )
    (comp (ref "C46")
      (value "2.2uF")
      (footprint "easyedapro:C0201")
      (description "Capacitance:2.2uF Tolerance:±20% Tolerance:±20% Voltage Rating:6.3V Temperature Coefficient:X5R")
      (fields
        (field (name "Manufacturer Part") "GRM033R60J225ME47D")
        (field (name "Manufacturer") "muRata(村田)")
      )
      (libsource (lib "easyedapro") (part "GRM033R60J225ME47D"))
    )
    (comp (ref "C47")
      (value "2.2uF")
      (footprint "easyedapro:C0201")
      (description "Capacitance:2.2uF Tolerance:±20% Tolerance:±20% Voltage Rating:6.3V Temperature Coefficient:X5R")
      (fields
        (field (name "Manufacturer Part") "GRM033R60J225ME47D")
        (field (name "Manufacturer") "muRata(村田)")
      )
      (libsource (lib "easyedapro") (part "GRM033R60J225ME47D"))
    )
    (comp (ref "C48")
      (value "2.2uF")
      (footprint "easyedapro:C0201")
      (description "Capacitance:2.2uF Tolerance:±20% Tolerance:±20% Voltage Rating:6.3V Temperature Coefficient:X5R")
      (fields
        (field (name "Manufacturer Part") "GRM033R60J225ME47D")
        (field (name "Manufacturer") "muRata(村田)")
      )
      (libsource (lib "easyedapro") (part "GRM033R60J225ME47D"))
    )
    (comp (ref "C50")
      (value "2.2uF")
      (footprint "easyedapro:C0201")
      (description "Capacitance:2.2uF Tolerance:±20% Tolerance:±20% Voltage Rating:6.3V Temperature Coefficient:X5R")
      (fields
        (field (name "Manufacturer Part") "GRM033R60J225ME47D")
        (field (name "Manufacturer") "muRata(村田)")
      )
      (libsource (lib "easyedapro") (part "GRM033R60J225ME47D"))
    )
    (comp (ref "C65")
      (value "100nF")
      (footprint "easyedapro:C0201")
      (description "Capacitance:100nF Tolerance:±10% Tolerance:±10% Voltage Rating:10V Temperature Coefficient:X5R")
      (fields
        (field (name "Manufacturer Part") "CL03A104KP3NNNC")
        (field (name "Manufacturer") "SAMSUNG(三星)")
      )
      (libsource (lib "easyedapro") (part "CL03A104KP3NNNC"))
    )
    (comp (ref "FPC1")
      (value "FPC-0.5FX-18PWBH15")
      (footprint "easyedapro:FPC-SMD_18P-P0.50_XUNPU_FPC-0.5FX-18PWBH15")
      (fields (field (name "Manufacturer") "XUNPU(讯普)"))
      (libsource (lib "easyedapro") (part "FPC-0.5FX-18PWBH15"))
    )
    (comp (ref "FPC2")
      (value "FPC06-T1T1-2021-A")
      (footprint "easyedapro:FPC-SMD_FPC06-T1T1-2021-A")
      (fields (field (name "Manufacturer") "SHETIME(高钺达)"))
      (libsource (lib "easyedapro") (part "FPC06-T1T1-2021-A"))
    )
    (comp (ref "FPC3")
      (value "FPC-0.5FX-24PH20")
      (footprint "easyedapro:FPC-SMD_24P-P0.50_YUANDI_FPC-0.5FX-24PH20")
      (fields (field (name "Manufacturer") "Yuandi(元迪)"))
      (libsource (lib "easyedapro") (part "FPC-0.5FX-24PH20"))
    )
    (comp (ref "Q4")
      (value "MMBT3904")
      (footprint "easyedapro:SOT-23-3_L2.9-W1.3-P1.90-LS2.4-BR")
      (fields (field (name "Manufacturer") "DOWO(东沃)"))
      (libsource (lib "easyedapro") (part "MMBT3904_C22374713"))
    )
    (comp (ref "R17")
      (value "4.7Ω")
      (fields
        (field (name "Manufacturer Part") "0603WAF470KT5E")
        (field (name "Manufacturer") "UNI-ROYAL(厚声)")
      )
      (libsource (lib "easyedapro") (part "0603WAF470KT5E"))
    )
    (comp (ref "R18")
      (value "10kΩ")
      (footprint "easyedapro:R0201")
      (fields
        (field (name "Manufacturer Part") "0201WMF1002TEE")
        (field (name "Manufacturer") "UNI-ROYAL(厚声)")
      )
      (libsource (lib "easyedapro") (part "0201WMF1002TEE"))
    )
    (comp (ref "R19")
      (value "2kΩ")
      (footprint "easyedapro:R0201")
      (fields
        (field (name "Manufacturer Part") "0201WMF2001TEE")
        (field (name "Manufacturer") "UNI-ROYAL(厚声)")
      )
      (libsource (lib "easyedapro") (part "0201WMF2001TEE"))
    )
    (comp (ref "R20")
      (value "10kΩ")
      (footprint "easyedapro:R0201")
      (fields
        (field (name "Manufacturer Part") "0201WMF1002TEE")
        (field (name "Manufacturer") "UNI-ROYAL(厚声)")
      )
      (libsource (lib "easyedapro") (part "0201WMF1002TEE"))
    )
    (comp (ref "R32")
      (value "0Ω")
      (footprint "easyedapro:R0603")
      (fields
        (field (name "Manufacturer Part") "0603WAF0000T5E")
        (field (name "Manufacturer") "UNI-ROYAL(厚声)")
      )
      (libsource (lib "easyedapro") (part "0603WAF0000T5E"))
    )
    (comp (ref "R33")
      (value "10kΩ")
      (footprint "easyedapro:R0201")
      (fields
        (field (name "Manufacturer Part") "0201WMF1002TEE")
        (field (name "Manufacturer") "UNI-ROYAL(厚声)")
      )
      (libsource (lib "easyedapro") (part "0201WMF1002TEE"))
    )
    (comp (ref "R34")
      (value "10kΩ")
      (footprint "easyedapro:R0201")
      (fields
        (field (name "Manufacturer Part") "0201WMF1002TEE")
        (field (name "Manufacturer") "UNI-ROYAL(厚声)")
      )
      (libsource (lib "easyedapro") (part "0201WMF1002TEE"))
    )
    (comp (ref "U10")
      (value "TSC2007IPWR")
      (footprint "easyedapro:TSSOP-16_L5.0-W4.4-P0.65-LS6.4-BL")
      (fields (field (name "Manufacturer") "TI(德州仪器)"))
      (libsource (lib "easyedapro") (part "TSC2007IPWR"))
    )
    (comp (ref "U11")
      (value "BL8555-28PRA")
      (footprint "easyedapro:SOT-23-5_L3.0-W1.7-P0.95-LS2.8-BL")
      (fields (field (name "Manufacturer") "BL(上海贝岭)"))
      (libsource (lib "easyedapro") (part "BL8555-28PRA"))
    )
    (comp (ref "U12")
      (value "AP7343Q-18W5-7")
      (footprint "easyedapro:SOT-23-5_L3.0-W1.7-P0.95-LS2.8-BR")
      (fields (field (name "Manufacturer") "DIODES(美台)"))
      (libsource (lib "easyedapro") (part "AP7343Q-18W5-7_C3746471"))
    )
    (comp (ref "BOOT")
      (value "B3U-1000P")
      (footprint "easyedapro:KEY-SMD_B3U-1000PM")
      (fields (field (name "Manufacturer") "OMRON(欧姆龙)"))
      (libsource (lib "easyedapro") (part "B3U-1000P"))
    )
    (comp (ref "C3")
      (value "1uF")
      (footprint "easyedapro:C0201")
      (description "Capacitance:1uF Tolerance:±20% Tolerance:±20% Voltage Rating:6.3V Temperature Coefficient:X5R")
      (fields
        (field (name "Manufacturer Part") "CL03A105MQ3CSNH")
        (field (name "Manufacturer") "SAMSUNG(三星)")
      )
      (libsource (lib "easyedapro") (part "CL03A105MQ3CSNH"))
    )
    (comp (ref "C20")
      (value "100nF")
      (footprint "easyedapro:C0201")
      (description "Capacitance:100nF Tolerance:±10% Tolerance:±10% Voltage Rating:10V Temperature Coefficient:X5R")
      (fields
        (field (name "Manufacturer Part") "CL03A104KP3NNNC")
        (field (name "Manufacturer") "SAMSUNG(三星)")
      )
      (libsource (lib "easyedapro") (part "CL03A104KP3NNNC"))
    )
    (comp (ref "C21")
      (value "100nF")
      (footprint "easyedapro:C0201")
      (description "Capacitance:100nF Tolerance:±10% Tolerance:±10% Voltage Rating:10V Temperature Coefficient:X5R")
      (fields
        (field (name "Manufacturer Part") "CL03A104KP3NNNC")
        (field (name "Manufacturer") "SAMSUNG(三星)")
      )
      (libsource (lib "easyedapro") (part "CL03A104KP3NNNC"))
    )
    (comp (ref "C22")
      (value "100nF")
      (footprint "easyedapro:C0201")
      (description "Capacitance:100nF Tolerance:±10% Tolerance:±10% Voltage Rating:10V Temperature Coefficient:X5R")
      (fields
        (field (name "Manufacturer Part") "CL03A104KP3NNNC")
        (field (name "Manufacturer") "SAMSUNG(三星)")
      )
      (libsource (lib "easyedapro") (part "CL03A104KP3NNNC"))
    )
    (comp (ref "C23")
      (value "100nF")
      (footprint "easyedapro:C0201")
      (description "Capacitance:100nF Tolerance:±10% Tolerance:±10% Voltage Rating:10V Temperature Coefficient:X5R")
      (fields
        (field (name "Manufacturer Part") "CL03A104KP3NNNC")
        (field (name "Manufacturer") "SAMSUNG(三星)")
      )
      (libsource (lib "easyedapro") (part "CL03A104KP3NNNC"))
    )
    (comp (ref "C24")
      (value "100nF")
      (footprint "easyedapro:C0201")
      (description "Capacitance:100nF Tolerance:±10% Tolerance:±10% Voltage Rating:10V Temperature Coefficient:X5R")
      (fields
        (field (name "Manufacturer Part") "CL03A104KP3NNNC")
        (field (name "Manufacturer") "SAMSUNG(三星)")
      )
      (libsource (lib "easyedapro") (part "CL03A104KP3NNNC"))
    )
    (comp (ref "IND")
      (value "KT-0603YG")
      (footprint "easyedapro:LED0603-RD")
      (fields (field (name "Manufacturer") "KENTO"))
      (libsource (lib "easyedapro") (part "XL-0603QYGC"))
    )
    (comp (ref "PB1")
      (value "TS24CA")
      (footprint "easyedapro:SW-SMD_2P-TS24CA")
      (fields (field (name "Manufacturer") "SHOU HAN(首韩)"))
      (libsource (lib "easyedapro") (part "TS24CA"))
    )
    (comp (ref "PB2")
      (value "TS24CA")
      (footprint "easyedapro:SW-SMD_2P-TS24CA")
      (fields (field (name "Manufacturer") "SHOU HAN(首韩)"))
      (libsource (lib "easyedapro") (part "TS24CA"))
    )
    (comp (ref "PWR")
      (value "KT-0603R")
      (fields (field (name "Manufacturer") "KENTO"))
      (libsource (lib "easyedapro") (part "KT-0603R"))
    )
    (comp (ref "R1")
      (value "10kΩ")
      (footprint "easyedapro:R0201")
      (fields
        (field (name "Manufacturer Part") "0201WMF1002TEE")
        (field (name "Manufacturer") "UNI-ROYAL(厚声)")
      )
      (libsource (lib "easyedapro") (part "0201WMF1002TEE"))
    )
    (comp (ref "R4")
      (value "10kΩ")
      (footprint "easyedapro:R0201")
      (fields
        (field (name "Manufacturer Part") "0201WMF1002TEE")
        (field (name "Manufacturer") "UNI-ROYAL(厚声)")
      )
      (libsource (lib "easyedapro") (part "0201WMF1002TEE"))
    )
    (comp (ref "R6")
      (value "10kΩ")
      (footprint "easyedapro:R0201")
      (fields
        (field (name "Manufacturer Part") "0201WMF1002TEE")
        (field (name "Manufacturer") "UNI-ROYAL(厚声)")
      )
      (libsource (lib "easyedapro") (part "0201WMF1002TEE"))
    )
    (comp (ref "R7")
      (value "10kΩ")
      (footprint "easyedapro:R0201")
      (fields
        (field (name "Manufacturer Part") "0201WMF1002TEE")
        (field (name "Manufacturer") "UNI-ROYAL(厚声)")
      )
      (libsource (lib "easyedapro") (part "0201WMF1002TEE"))
    )
    (comp (ref "R15")
      (value "2kΩ")
      (footprint "easyedapro:R0201")
      (fields
        (field (name "Manufacturer Part") "0201WMF2001TEE")
        (field (name "Manufacturer") "UNI-ROYAL(厚声)")
      )
      (libsource (lib "easyedapro") (part "0201WMF2001TEE"))
    )
    (comp (ref "R16")
      (value "2kΩ")
      (footprint "easyedapro:R0201")
      (fields
        (field (name "Manufacturer Part") "0201WMF2001TEE")
        (field (name "Manufacturer") "UNI-ROYAL(厚声)")
      )
      (libsource (lib "easyedapro") (part "0201WMF2001TEE"))
    )
    (comp (ref "R37")
      (value "10kΩ")
      (footprint "easyedapro:R0201")
      (fields
        (field (name "Manufacturer Part") "0201WMF1002TEE")
        (field (name "Manufacturer") "UNI-ROYAL(厚声)")
      )
      (libsource (lib "easyedapro") (part "0201WMF1002TEE"))
    )
    (comp (ref "R38")
      (value "10kΩ")
      (footprint "easyedapro:R0201")
      (fields
        (field (name "Manufacturer Part") "0201WMF1002TEE")
        (field (name "Manufacturer") "UNI-ROYAL(厚声)")
      )
      (libsource (lib "easyedapro") (part "0201WMF1002TEE"))
    )
    (comp (ref "R39")
      (value "10kΩ")
      (footprint "easyedapro:R0201")
      (fields
        (field (name "Manufacturer Part") "0201WMF1002TEE")
        (field (name "Manufacturer") "UNI-ROYAL(厚声)")
      )
      (libsource (lib "easyedapro") (part "0201WMF1002TEE"))
    )
    (comp (ref "RGB1")
      (value "XL-0807RGBC-2812B")
      (footprint "easyedapro:LED-SMD_4P-L2.0-W1.8_XL-0807RGBC-WS2812B")
      (fields (field (name "Manufacturer") "XINGLIGHT(成兴光)"))
      (libsource (lib "easyedapro") (part "XL-0807RGBC-WS2812B"))
    )
    (comp (ref "RGB2")
      (value "XL-0807RGBC-2812B")
      (footprint "easyedapro:LED-SMD_4P-L2.0-W1.8_XL-0807RGBC-WS2812B")
      (fields (field (name "Manufacturer") "XINGLIGHT(成兴光)"))
      (libsource (lib "easyedapro") (part "XL-0807RGBC-WS2812B"))
    )
    (comp (ref "RST")
      (value "B3U-1000P")
      (footprint "easyedapro:KEY-SMD_B3U-1000PM")
      (fields (field (name "Manufacturer") "OMRON(欧姆龙)"))
      (libsource (lib "easyedapro") (part "B3U-1000P"))
    )
    (comp (ref "SW1")
      (value "EVQQ2B03W")
      (footprint "easyedapro:KEY-SMD_4P-L6.5-W6.0-P4.0-LS6.6")
      (fields (field (name "Manufacturer") "PANASONIC(松下)"))
      (libsource (lib "easyedapro") (part "EVQQ2B03W"))
    )
    (comp (ref "SW2")
      (value "EVQQ2B03W")
      (footprint "easyedapro:KEY-SMD_4P-L6.5-W6.0-P4.0-LS6.6")
      (fields (field (name "Manufacturer") "PANASONIC(松下)"))
      (libsource (lib "easyedapro") (part "EVQQ2B03W"))
    )
    (comp (ref "SW3")
      (value "EVQQ2B03W")
      (footprint "easyedapro:KEY-SMD_4P-L6.5-W6.0-P4.0-LS6.6")
      (fields (field (name "Manufacturer") "PANASONIC(松下)"))
      (libsource (lib "easyedapro") (part "EVQQ2B03W"))
    )
    (comp (ref "C2")
      (value "22uF")
      (description "Capacitance:22uF Tolerance:±20% Tolerance:±20% Voltage Rating:6.3V Temperature Coefficient:X5R")
      (fields
        (field (name "Manufacturer Part") "CL05A226MQ5QUNC")
        (field (name "Manufacturer") "SAMSUNG(三星)")
      )
      (libsource (lib "easyedapro") (part "CL05A226MQ5QUNC"))
    )
    (comp (ref "C6")
      (value "15pF")
      (footprint "easyedapro:C0201")
      (description "Capacitance:15pF Tolerance:±5% Tolerance:±5% Voltage Rating:50V Temperature Coefficient:C0G")
      (fields
        (field (name "Manufacturer Part") "GRM0335C1H150JA01D")
        (field (name "Manufacturer") "muRata(村田)")
      )
      (libsource (lib "easyedapro") (part "GRM0335C1H150JA01D"))
    )
    (comp (ref "C18")
      (value "100nF")
      (footprint "easyedapro:C0201")
      (description "Capacitance:100nF Tolerance:±10% Tolerance:±10% Voltage Rating:10V Temperature Coefficient:X5R")
      (fields
        (field (name "Manufacturer Part") "CL03A104KP3NNNC")
        (field (name "Manufacturer") "SAMSUNG(三星)")
      )
      (libsource (lib "easyedapro") (part "CL03A104KP3NNNC"))
    )
    (comp (ref "C26")
      (value "1uF")
      (footprint "easyedapro:C0201")
      (description "Capacitance:1uF Tolerance:±20% Tolerance:±20% Voltage Rating:6.3V Temperature Coefficient:X5R")
      (fields
        (field (name "Manufacturer Part") "CL03A105MQ3CSNH")
        (field (name "Manufacturer") "SAMSUNG(三星)")
      )
      (libsource (lib "easyedapro") (part "CL03A105MQ3CSNH"))
    )
    (comp (ref "C27")
      (value "1uF")
      (footprint "easyedapro:C0201")
      (description "Capacitance:1uF Tolerance:±20% Tolerance:±20% Voltage Rating:6.3V Temperature Coefficient:X5R")
      (fields
        (field (name "Manufacturer Part") "CL03A105MQ3CSNH")
        (field (name "Manufacturer") "SAMSUNG(三星)")
      )
      (libsource (lib "easyedapro") (part "CL03A105MQ3CSNH"))
    )
    (comp (ref "C28")
      (value "1uF")
      (footprint "easyedapro:C0201")
      (description "Capacitance:1uF Tolerance:±20% Tolerance:±20% Voltage Rating:6.3V Temperature Coefficient:X5R")
      (fields
        (field (name "Manufacturer Part") "CL03A105MQ3CSNH")
        (field (name "Manufacturer") "SAMSUNG(三星)")
      )
      (libsource (lib "easyedapro") (part "CL03A105MQ3CSNH"))
    )
    (comp (ref "C29")
      (value "100nF")
      (footprint "easyedapro:C0201")
      (description "Capacitance:100nF Tolerance:±10% Tolerance:±10% Voltage Rating:10V Temperature Coefficient:X5R")
      (fields
        (field (name "Manufacturer Part") "CL03A104KP3NNNC")
        (field (name "Manufacturer") "SAMSUNG(三星)")
      )
      (libsource (lib "easyedapro") (part "CL03A104KP3NNNC"))
    )
    (comp (ref "C30")
      (value "100nF")
      (footprint "easyedapro:C0201")
      (description "Capacitance:100nF Tolerance:±10% Tolerance:±10% Voltage Rating:10V Temperature Coefficient:X5R")
      (fields
        (field (name "Manufacturer Part") "CL03A104KP3NNNC")
        (field (name "Manufacturer") "SAMSUNG(三星)")
      )
      (libsource (lib "easyedapro") (part "CL03A104KP3NNNC"))
    )
    (comp (ref "C36")
      (value "100nF")
      (footprint "easyedapro:C0201")
      (description "Capacitance:100nF Tolerance:±10% Tolerance:±10% Voltage Rating:10V Temperature Coefficient:X5R")
      (fields
        (field (name "Manufacturer Part") "CL03A104KP3NNNC")
        (field (name "Manufacturer") "SAMSUNG(三星)")
      )
      (libsource (lib "easyedapro") (part "CL03A104KP3NNNC"))
    )
    (comp (ref "C37")
      (value "1uF")
      (footprint "easyedapro:C0201")
      (description "Capacitance:1uF Tolerance:±20% Tolerance:±20% Voltage Rating:6.3V Temperature Coefficient:X5R")
      (fields
        (field (name "Manufacturer Part") "CL03A105MQ3CSNH")
        (field (name "Manufacturer") "SAMSUNG(三星)")
      )
      (libsource (lib "easyedapro") (part "CL03A105MQ3CSNH"))
    )
    (comp (ref "C38")
      (value "1uF")
      (footprint "easyedapro:C0201")
      (description "Capacitance:1uF Tolerance:±20% Tolerance:±20% Voltage Rating:6.3V Temperature Coefficient:X5R")
      (fields
        (field (name "Manufacturer Part") "CL03A105MQ3CSNH")
        (field (name "Manufacturer") "SAMSUNG(三星)")
      )
      (libsource (lib "easyedapro") (part "CL03A105MQ3CSNH"))
    )
    (comp (ref "C39")
      (value "1uF")
      (footprint "easyedapro:C0201")
      (description "Capacitance:1uF Tolerance:±20% Tolerance:±20% Voltage Rating:6.3V Temperature Coefficient:X5R")
      (fields
        (field (name "Manufacturer Part") "CL03A105MQ3CSNH")
        (field (name "Manufacturer") "SAMSUNG(三星)")
      )
      (libsource (lib "easyedapro") (part "CL03A105MQ3CSNH"))
    )
    (comp (ref "C40")
      (value "15pF")
      (footprint "easyedapro:C0201")
      (description "Capacitance:15pF Tolerance:±5% Tolerance:±5% Voltage Rating:50V Temperature Coefficient:C0G")
      (fields
        (field (name "Manufacturer Part") "GRM0335C1H150JA01D")
        (field (name "Manufacturer") "muRata(村田)")
      )
      (libsource (lib "easyedapro") (part "GRM0335C1H150JA01D"))
    )
    (comp (ref "C41")
      (value "100nF")
      (footprint "easyedapro:C0201")
      (description "Capacitance:100nF Tolerance:±10% Tolerance:±10% Voltage Rating:10V Temperature Coefficient:X5R")
      (fields
        (field (name "Manufacturer Part") "CL03A104KP3NNNC")
        (field (name "Manufacturer") "SAMSUNG(三星)")
      )
      (libsource (lib "easyedapro") (part "CL03A104KP3NNNC"))
    )
    (comp (ref "C42")
      (value "1uF")
      (footprint "easyedapro:C0201")
      (description "Capacitance:1uF Tolerance:±20% Tolerance:±20% Voltage Rating:6.3V Temperature Coefficient:X5R")
      (fields
        (field (name "Manufacturer Part") "CL03A105MQ3CSNH")
        (field (name "Manufacturer") "SAMSUNG(三星)")
      )
      (libsource (lib "easyedapro") (part "CL03A105MQ3CSNH"))
    )
    (comp (ref "C43")
      (value "1uF")
      (footprint "easyedapro:C0201")
      (description "Capacitance:1uF Tolerance:±20% Tolerance:±20% Voltage Rating:6.3V Temperature Coefficient:X5R")
      (fields
        (field (name "Manufacturer Part") "CL03A105MQ3CSNH")
        (field (name "Manufacturer") "SAMSUNG(三星)")
      )
      (libsource (lib "easyedapro") (part "CL03A105MQ3CSNH"))
    )
    (comp (ref "C45")
      (value "22uF")
      (description "Capacitance:22uF Tolerance:±20% Tolerance:±20% Voltage Rating:6.3V Temperature Coefficient:X5R")
      (fields
        (field (name "Manufacturer Part") "CL05A226MQ5QUNC")
        (field (name "Manufacturer") "SAMSUNG(三星)")
      )
      (libsource (lib "easyedapro") (part "CL05A226MQ5QUNC"))
    )
    (comp (ref "MIC1")
      (value "MSM381ACP003")
      (footprint "easyedapro:MIC-SMD_4P-L2.8-W1.9-TR_MSM381ACP003")
      (fields (field (name "Manufacturer") "MEMS(敏芯微)"))
      (libsource (lib "easyedapro") (part "MSM381ACP003_C51928212"))
    )
    (comp (ref "MIC2")
      (value "MSM381ACP003")
      (footprint "easyedapro:MIC-SMD_4P-L2.8-W1.9-TR_MSM381ACP003")
      (fields (field (name "Manufacturer") "MEMS(敏芯微)"))
      (libsource (lib "easyedapro") (part "MSM381ACP003_C51928212"))
    )
    (comp (ref "R21")
      (value "3.3kΩ")
      (footprint "easyedapro:R0201")
      (fields
        (field (name "Manufacturer Part") "0201WMF3301TEE")
        (field (name "Manufacturer") "UNI-ROYAL(厚声)")
      )
      (libsource (lib "easyedapro") (part "0201WMF3301TEE"))
    )
    (comp (ref "R22")
      (value "0Ω")
      (footprint "easyedapro:R0603")
      (fields
        (field (name "Manufacturer Part") "0603WAF0000T5E")
        (field (name "Manufacturer") "UNI-ROYAL(厚声)")
      )
      (libsource (lib "easyedapro") (part "0603WAF0000T5E"))
    )
    (comp (ref "R35")
      (value "10kΩ")
      (footprint "easyedapro:R0201")
      (fields
        (field (name "Manufacturer Part") "0201WMF1002TEE")
        (field (name "Manufacturer") "UNI-ROYAL(厚声)")
      )
      (libsource (lib "easyedapro") (part "0201WMF1002TEE"))
    )
    (comp (ref "R36")
      (value "10kΩ")
      (footprint "easyedapro:R0201")
      (fields
        (field (name "Manufacturer Part") "0201WMF1002TEE")
        (field (name "Manufacturer") "UNI-ROYAL(厚声)")
      )
      (libsource (lib "easyedapro") (part "0201WMF1002TEE"))
    )
    (comp (ref "SP1")
      (value "SM02B-SRSS-TB(LF)(SN)")
      (footprint "easyedapro:CONN-SMD_2P-P1.00_SM02B-SRSS-TB-LF-SN")
      (fields (field (name "Manufacturer") "JST"))
      (libsource (lib "easyedapro") (part "SM02B-SRSS-TB (LF)(SN)"))
    )
    (comp (ref "U13")
      (value "NS4168")
      (footprint "easyedapro:ESOP-8_L4.9-W3.9-P1.27-LS6.0-BL-EP")
      (description "Class:Class D Output Power:2.5Wx1@4Ω Voltage - Supply:3V~5.5V Voltage - Supply:3V~5.5V")
      (fields (field (name "Manufacturer") "Nsiway(纳芯威)"))
      (libsource (lib "easyedapro") (part "NS4168_C910588"))
    )
    (comp (ref "U14")
      (value "ES7243E")
      (footprint "easyedapro:QFN-20_L3.0-W3.0-P0.40-BL-EP1.7")
      (fields (field (name "Manufacturer") "Everest-semi(顺芯)"))
      (libsource (lib "easyedapro") (part "ES7243E"))
    )
  )
  (nets
    (net (code "1") (name "1V8") (class "Default")
      (node (ref "C50") (pin "2") (pinfunction "2_2") (pintype "input"))
      (node (ref "FPC3") (pin "15") (pinfunction "15_15") (pintype "unspecified"))
      (node (ref "U12") (pin "5") (pinfunction "VOUT_5") (pintype "unspecified"))
    )
    (net (code "2") (name "2V8") (class "Default")
      (node (ref "C47") (pin "2") (pinfunction "2_2") (pintype "input"))
      (node (ref "FPC3") (pin "14") (pinfunction "14_14") (pintype "unspecified"))
      (node (ref "FPC3") (pin "21") (pinfunction "21_21") (pintype "unspecified"))
      (node (ref "U11") (pin "5") (pinfunction "VOUT_5") (pintype "unspecified"))
    )
    (net (code "3") (name "3V3") (class "Default")
      (node (ref "C1") (pin "2") (pinfunction "2_2") (pintype "input"))
      (node (ref "C12") (pin "2") (pinfunction "2_2") (pintype "unspecified"))
      (node (ref "C18") (pin "2") (pinfunction "2_2") (pintype "unspecified"))
      (node (ref "C19") (pin "2") (pinfunction "2_2") (pintype "unspecified"))
      (node (ref "C2") (pin "2") (pinfunction "2_2") (pintype "unspecified"))
      (node (ref "C22") (pin "2") (pinfunction "2_2") (pintype "unspecified"))
      (node (ref "C23") (pin "2") (pinfunction "2_2") (pintype "unspecified"))
      (node (ref "C24") (pin "2") (pinfunction "2_2") (pintype "unspecified"))
      (node (ref "C26") (pin "2") (pinfunction "2_2") (pintype "input"))
      (node (ref "C29") (pin "2") (pinfunction "2_2") (pintype "unspecified"))
      (node (ref "C30") (pin "2") (pinfunction "2_2") (pintype "unspecified"))
      (node (ref "C36") (pin "2") (pinfunction "2_2") (pintype "unspecified"))
      (node (ref "C37") (pin "2") (pinfunction "2_2") (pintype "input"))
      (node (ref "C41") (pin "2") (pinfunction "2_2") (pintype "unspecified"))
      (node (ref "C45") (pin "2") (pinfunction "2_2") (pintype "unspecified"))
      (node (ref "C46") (pin "2") (pinfunction "2_2") (pintype "input"))
      (node (ref "C48") (pin "2") (pinfunction "2_2") (pintype "input"))
      (node (ref "C59") (pin "2") (pinfunction "2_2") (pintype "unspecified"))
      (node (ref "C60") (pin "2") (pinfunction "2_2") (pintype "unspecified"))
      (node (ref "C61") (pin "2") (pinfunction "2_2") (pintype "unspecified"))
      (node (ref "C62") (pin "2") (pinfunction "2_2") (pintype "unspecified"))
      (node (ref "C63") (pin "2") (pinfunction "2_2") (pintype "unspecified"))
      (node (ref "C64") (pin "2") (pinfunction "2_2") (pintype "unspecified"))
      (node (ref "C65") (pin "2") (pinfunction "2_2") (pintype "unspecified"))
      (node (ref "C_I2C") (pin "1") (pinfunction "1_1") (pintype "unspecified"))
      (node (ref "C_P0") (pin "1") (pinfunction "1_1") (pintype "unspecified"))
      (node (ref "C_P1-3") (pin "1") (pinfunction "1_1") (pintype "unspecified"))
      (node (ref "C_P4-7") (pin "1") (pinfunction "1_1") (pintype "unspecified"))
      (node (ref "FPC1") (pin "10") (pinfunction "10_10") (pintype "unspecified"))
      (node (ref "FPC1") (pin "9") (pinfunction "9_9") (pintype "unspecified"))
      (node (ref "FPC2") (pin "1") (pinfunction "1_1") (pintype "unspecified"))
      (node (ref "HUM") (pin "2") (pinfunction "VDD_2") (pintype "unspecified"))
      (node (ref "LS") (pin "1") (pinfunction "VDD_1") (pintype "unspecified"))
      (node (ref "MIC1") (pin "1") (pinfunction "VDD_1") (pintype "unspecified"))
      (node (ref "MIC2") (pin "1") (pinfunction "VDD_1") (pintype "unspecified"))
      (node (ref "R1") (pin "2") (pinfunction "2_2") (pintype "unspecified"))
      (node (ref "R12") (pin "1") (pinfunction "1_1") (pintype "unspecified"))
      (node (ref "R13") (pin "2") (pinfunction "2_2") (pintype "unspecified"))
      (node (ref "R14") (pin "2") (pinfunction "2_2") (pintype "unspecified"))
      (node (ref "R15") (pin "2") (pinfunction "2_2") (pintype "input"))
      (node (ref "R20") (pin "2") (pinfunction "2_2") (pintype "unspecified"))
      (node (ref "R23") (pin "2") (pinfunction "2_2") (pintype "input"))
      (node (ref "R29") (pin "2") (pinfunction "2_2") (pintype "unspecified"))
      (node (ref "R31") (pin "1") (pinfunction "1_1") (pintype "unspecified"))
      (node (ref "R33") (pin "1") (pinfunction "1_1") (pintype "unspecified"))
      (node (ref "R34") (pin "2") (pinfunction "2_2") (pintype "unspecified"))
      (node (ref "R35") (pin "1") (pinfunction "1_1") (pintype "unspecified"))
      (node (ref "R36") (pin "2") (pinfunction "2_2") (pintype "unspecified"))
      (node (ref "R37") (pin "2") (pinfunction "2_2") (pintype "unspecified"))
      (node (ref "R38") (pin "2") (pinfunction "2_2") (pintype "unspecified"))
      (node (ref "R39") (pin "2") (pinfunction "2_2") (pintype "unspecified"))
      (node (ref "R4") (pin "2") (pinfunction "2_2") (pintype "unspecified"))
      (node (ref "R43") (pin "2") (pinfunction "2_2") (pintype "unspecified"))
      (node (ref "R6") (pin "2") (pinfunction "2_2") (pintype "unspecified"))
      (node (ref "R7") (pin "2") (pinfunction "2_2") (pintype "unspecified"))
      (node (ref "RGB1") (pin "4") (pinfunction "VDD_4") (pintype "unspecified"))
      (node (ref "RGB2") (pin "4") (pinfunction "VDD_4") (pintype "unspecified"))
      (node (ref "TF1") (pin "4") (pinfunction "VDD_4") (pintype "unspecified"))
      (node (ref "U1") (pin "2") (pinfunction "3V3_2") (pintype "unspecified"))
      (node (ref "U10") (pin "1") (pinfunction "VDDREF_1") (pintype "unspecified"))
      (node (ref "U11") (pin "1") (pinfunction "VDD_1") (pintype "unspecified"))
      (node (ref "U11") (pin "3") (pinfunction "CE_3") (pintype "unspecified"))
      (node (ref "U12") (pin "1") (pinfunction "VIN_1") (pintype "unspecified"))
      (node (ref "U12") (pin "3") (pinfunction "EN_3") (pintype "unspecified"))
      (node (ref "U13") (pin "1") (pinfunction "CTRL_1") (pintype "unspecified"))
      (node (ref "U13") (pin "6") (pinfunction "VDD_6") (pintype "unspecified"))
      (node (ref "U14") (pin "1") (pinfunction "VDDP_1") (pintype "unspecified"))
      (node (ref "U14") (pin "12") (pinfunction "VDDA_12") (pintype "unspecified"))
      (node (ref "U14") (pin "17") (pinfunction "AD0_17") (pintype "unspecified"))
      (node (ref "U14") (pin "5") (pinfunction "VDDD_5") (pintype "unspecified"))
      (node (ref "U18") (pin "12") (pinfunction "VIN_12") (pintype "unspecified"))
      (node (ref "U2") (pin "8") (pinfunction "VCC_8") (pintype "unspecified"))
      (node (ref "U4") (pin "4") (pinfunction "VO_4") (pintype "unspecified"))
      (node (ref "U5") (pin "3") (pinfunction "VDDIO_3") (pintype "unspecified"))
      (node (ref "U5") (pin "7") (pinfunction "VDD_7") (pintype "unspecified"))
      (node (ref "U8") (pin "10") (pinfunction "VCC_10") (pintype "unspecified"))
      (node (ref "U9") (pin "21") (pinfunction "VCC_21") (pintype "unspecified"))
    )
    (net (code "4") (name "AGND") (class "Default")
      (node (ref "C18") (pin "1") (pinfunction "1_1") (pintype "unspecified"))
      (node (ref "C26") (pin "1") (pinfunction "1_1") (pintype "input"))
      (node (ref "C28") (pin "2") (pinfunction "2_2") (pintype "input"))
      (node (ref "C36") (pin "1") (pinfunction "1_1") (pintype "unspecified"))
      (node (ref "C37") (pin "1") (pinfunction "1_1") (pintype "input"))
      (node (ref "C39") (pin "2") (pinfunction "2_2") (pintype "input"))
      (node (ref "C40") (pin "1") (pinfunction "1_1") (pintype "input"))
      (node (ref "C42") (pin "1") (pinfunction "1_1") (pintype "input"))
      (node (ref "C43") (pin "1") (pinfunction "1_1") (pintype "input"))
      (node (ref "C6") (pin "1") (pinfunction "1_1") (pintype "input"))
      (node (ref "MIC1") (pin "3") (pinfunction "GND_3") (pintype "unspecified"))
      (node (ref "MIC1") (pin "4") (pinfunction "GND_4") (pintype "unspecified"))
      (node (ref "MIC2") (pin "3") (pinfunction "GND_3") (pintype "unspecified"))
      (node (ref "MIC2") (pin "4") (pinfunction "GND_4") (pintype "unspecified"))
      (node (ref "R22") (pin "1") (pinfunction "1_1") (pintype "input"))
    )
    (net (code "5") (name "BOOT") (class "Default")
      (node (ref "BOOT") (pin "2") (pinfunction "2_2") (pintype "unspecified"))
      (node (ref "R4") (pin "1") (pinfunction "1_1") (pintype "unspecified"))
      (node (ref "U1") (pin "27") (pinfunction "IO0_27") (pintype "unspecified"))
      (node (ref "U13") (pin "3") (pinfunction "BCLK_3") (pintype "unspecified"))
      (node (ref "U14") (pin "6") (pinfunction "SCLK_6") (pintype "unspecified"))
    )
    (net (code "6") (name "BUS_INT") (class "Default")
      (node (ref "R14") (pin "1") (pinfunction "1_1") (pintype "unspecified"))
      (node (ref "U1") (pin "37") (pinfunction "TXD0_37") (pintype "unspecified"))
      (node (ref "U9") (pin "22") (pinfunction "INT#_22") (pintype "unspecified"))
    )
    (net (code "7") (name "CC1") (class "Default")
      (node (ref "R5") (pin "1") (pinfunction "1_1") (pintype "input"))
      (node (ref "U3") (pin "3") (pinfunction "IO_3") (pintype "input"))
      (node (ref "USB1") (pin "A5") (pinfunction "CC1_A5") (pintype "unspecified"))
    )
    (net (code "8") (name "CC2") (class "Default")
      (node (ref "R3") (pin "2") (pinfunction "2_2") (pintype "input"))
      (node (ref "U3") (pin "1") (pinfunction "IO_1") (pintype "input"))
      (node (ref "USB1") (pin "B5") (pinfunction "CC2_B5") (pintype "unspecified"))
    )
    (net (code "9") (name "CS3") (class "Default")
      (node (ref "R28") (pin "2") (pinfunction "2_2") (pintype "unspecified"))
      (node (ref "TF1") (pin "2") (pinfunction "CD/DAT3_2") (pintype "unspecified"))
      (node (ref "U1") (pin "33") (pinfunction "IO40_33") (pintype "unspecified"))
    )
    (net (code "10") (name "C_D2") (class "Default")
      (node (ref "FPC3") (pin "6") (pinfunction "6_6") (pintype "unspecified"))
      (node (ref "U1") (pin "12") (pinfunction "IO8_12") (pintype "unspecified"))
    )
    (net (code "11") (name "C_D3") (class "Default")
      (node (ref "FPC3") (pin "4") (pinfunction "4_4") (pintype "unspecified"))
      (node (ref "U1") (pin "18") (pinfunction "IO10_18") (pintype "unspecified"))
    )
    (net (code "12") (name "C_D4") (class "Default")
      (node (ref "FPC3") (pin "3") (pinfunction "3_3") (pintype "unspecified"))
      (node (ref "U1") (pin "19") (pinfunction "IO11_19") (pintype "unspecified"))
    )
    (net (code "13") (name "C_D5") (class "Default")
      (node (ref "FPC3") (pin "5") (pinfunction "5_5") (pintype "unspecified"))
      (node (ref "U1") (pin "17") (pinfunction "IO9_17") (pintype "unspecified"))
    )
    (net (code "14") (name "C_D6") (class "Default")
      (node (ref "FPC3") (pin "7") (pinfunction "7_7") (pintype "unspecified"))
      (node (ref "U1") (pin "11") (pinfunction "IO18_11") (pintype "unspecified"))
    )
    (net (code "15") (name "C_D7") (class "Default")
      (node (ref "FPC3") (pin "9") (pinfunction "9_9") (pintype "unspecified"))
      (node (ref "U1") (pin "9") (pinfunction "IO16_9") (pintype "unspecified"))
    )
    (net (code "16") (name "C_D8") (class "Default")
      (node (ref "FPC3") (pin "11") (pinfunction "11_11") (pintype "unspecified"))
      (node (ref "U1") (pin "8") (pinfunction "IO15_8") (pintype "unspecified"))
    )
    (net (code "17") (name "C_D9") (class "Default")
      (node (ref "FPC3") (pin "13") (pinfunction "13_13") (pintype "unspecified"))
      (node (ref "U1") (pin "6") (pinfunction "IO6_6") (pintype "unspecified"))
    )
    (net (code "18") (name "C_HREF") (class "Default")
      (node (ref "FPC3") (pin "16") (pinfunction "16_16") (pintype "unspecified"))
      (node (ref "U1") (pin "5") (pinfunction "IO5_5") (pintype "unspecified"))
    )
    (net (code "19") (name "C_PCLK") (class "Default")
      (node (ref "FPC3") (pin "8") (pinfunction "8_8") (pintype "unspecified"))
      (node (ref "U1") (pin "10") (pinfunction "IO17_10") (pintype "unspecified"))
    )
    (net (code "20") (name "C_RST") (class "Default")
      (node (ref "FPC3") (pin "19") (pinfunction "19_19") (pintype "unspecified"))
      (node (ref "U9") (pin "3") (pinfunction "P02_3") (pintype "unspecified"))
    )
    (net (code "21") (name "C_VSYC") (class "Default")
      (node (ref "FPC3") (pin "18") (pinfunction "18_18") (pintype "unspecified"))
      (node (ref "U1") (pin "4") (pinfunction "IO4_4") (pintype "unspecified"))
    )
    (net (code "22") (name "C_XCLK") (class "Default")
      (node (ref "FPC3") (pin "12") (pinfunction "12_12") (pintype "unspecified"))
      (node (ref "U1") (pin "7") (pinfunction "IO7_7") (pintype "unspecified"))
    )
    (net (code "23") (name "DN") (class "Default")
      (node (ref "U1") (pin "13") (pinfunction "IO19_13") (pintype "unspecified"))
      (node (ref "U3") (pin "4") (pinfunction "IO_4") (pintype "input"))
      (node (ref "USB1") (pin "A7") (pinfunction "DN1_A7") (pintype "unspecified"))
      (node (ref "USB1") (pin "B7") (pinfunction "DN2_B7") (pintype "unspecified"))
    )
    (net (code "24") (name "DP") (class "Default")
      (node (ref "U1") (pin "14") (pinfunction "IO20_14") (pintype "unspecified"))
      (node (ref "U3") (pin "6") (pinfunction "IO_6") (pintype "input"))
      (node (ref "USB1") (pin "A6") (pinfunction "DP1_A6") (pintype "unspecified"))
      (node (ref "USB1") (pin "B6") (pinfunction "DP2_B6") (pintype "unspecified"))
    )
    (net (code "25") (name "GND") (class "Default")
      (node (ref "BATT") (pin "1") (pinfunction "1_1") (pintype "unspecified"))
      (node (ref "BATT") (pin "3") (pinfunction "3_3") (pintype "unspecified"))
      (node (ref "BATT") (pin "4") (pinfunction "4_4") (pintype "unspecified"))
      (node (ref "BOOT") (pin "1") (pinfunction "1_1") (pintype "unspecified"))
      (node (ref "C1") (pin "1") (pinfunction "1_1") (pintype "input"))
      (node (ref "C12") (pin "1") (pinfunction "1_1") (pintype "unspecified"))
      (node (ref "C19") (pin "1") (pinfunction "1_1") (pintype "unspecified"))
      (node (ref "C2") (pin "1") (pinfunction "1_1") (pintype "unspecified"))
      (node (ref "C20") (pin "1") (pinfunction "1_1") (pintype "unspecified"))
      (node (ref "C21") (pin "1") (pinfunction "1_1") (pintype "unspecified"))
      (node (ref "C22") (pin "1") (pinfunction "1_1") (pintype "unspecified"))
      (node (ref "C23") (pin "1") (pinfunction "1_1") (pintype "unspecified"))
      (node (ref "C24") (pin "1") (pinfunction "1_1") (pintype "unspecified"))
      (node (ref "C25") (pin "1") (pinfunction "1_1") (pintype "unspecified"))
      (node (ref "C29") (pin "1") (pinfunction "1_1") (pintype "unspecified"))
      (node (ref "C3") (pin "1") (pinfunction "1_1") (pintype "input"))
      (node (ref "C30") (pin "1") (pinfunction "1_1") (pintype "unspecified"))
      (node (ref "C41") (pin "1") (pinfunction "1_1") (pintype "unspecified"))
      (node (ref "C45") (pin "1") (pinfunction "1_1") (pintype "unspecified"))
      (node (ref "C46") (pin "1") (pinfunction "1_1") (pintype "input"))
      (node (ref "C47") (pin "1") (pinfunction "1_1") (pintype "input"))
      (node (ref "C48") (pin "1") (pinfunction "1_1") (pintype "input"))
      (node (ref "C50") (pin "1") (pinfunction "1_1") (pintype "input"))
      (node (ref "C51") (pin "1") (pinfunction "1_1") (pintype "unspecified"))
      (node (ref "C52") (pin "1") (pinfunction "1_1") (pintype "unspecified"))
      (node (ref "C54") (pin "2") (pinfunction "2_2") (pintype "unspecified"))
      (node (ref "C58") (pin "1") (pinfunction "1_1") (pintype "unspecified"))
      (node (ref "C59") (pin "1") (pinfunction "1_1") (pintype "unspecified"))
      (node (ref "C60") (pin "1") (pinfunction "1_1") (pintype "unspecified"))
      (node (ref "C61") (pin "1") (pinfunction "1_1") (pintype "unspecified"))
      (node (ref "C62") (pin "1") (pinfunction "1_1") (pintype "unspecified"))
      (node (ref "C63") (pin "1") (pinfunction "1_1") (pintype "unspecified"))
      (node (ref "C64") (pin "1") (pinfunction "1_1") (pintype "unspecified"))
      (node (ref "C65") (pin "1") (pinfunction "1_1") (pintype "unspecified"))
      (node (ref "C66") (pin "1") (pinfunction "1_1") (pintype "input"))
      (node (ref "C67") (pin "1") (pinfunction "1_1") (pintype "unspecified"))
      (node (ref "C_I2C") (pin "2") (pinfunction "2_2") (pintype "unspecified"))
      (node (ref "C_I2C") (pin "5") (pinfunction "5_5") (pintype "unspecified"))
      (node (ref "C_I2C") (pin "6") (pinfunction "6_6") (pintype "unspecified"))
      (node (ref "C_P0") (pin "2") (pinfunction "2_2") (pintype "unspecified"))
      (node (ref "C_P0") (pin "4") (pinfunction "4_4") (pintype "unspecified"))
      (node (ref "C_P0") (pin "5") (pinfunction "5_5") (pintype "unspecified"))
      (node (ref "C_P1-3") (pin "2") (pinfunction "2_2") (pintype "unspecified"))
      (node (ref "C_P1-3") (pin "6") (pinfunction "6_6") (pintype "unspecified"))
      (node (ref "C_P1-3") (pin "7") (pinfunction "7_7") (pintype "unspecified"))
      (node (ref "C_P4-7") (pin "2") (pinfunction "2_2") (pintype "unspecified"))
      (node (ref "C_P4-7") (pin "7") (pinfunction "7_7") (pintype "unspecified"))
      (node (ref "C_P4-7") (pin "8") (pinfunction "8_8") (pintype "unspecified"))
      (node (ref "D5") (pin "1") (pinfunction "1_1") (pintype "unspecified"))
      (node (ref "FPC1") (pin "11") (pinfunction "11_11") (pintype "unspecified"))
      (node (ref "FPC1") (pin "12") (pinfunction "12_12") (pintype "unspecified"))
      (node (ref "FPC1") (pin "18") (pinfunction "18_18") (pintype "unspecified"))
      (node (ref "FPC1") (pin "19") (pinfunction "19_19") (pintype "unspecified"))
      (node (ref "FPC1") (pin "20") (pinfunction "20_20") (pintype "unspecified"))
      (node (ref "FPC2") (pin "6") (pinfunction "6_6") (pintype "unspecified"))
      (node (ref "FPC2") (pin "7") (pinfunction "7_7") (pintype "unspecified"))
      (node (ref "FPC2") (pin "8") (pinfunction "8_8") (pintype "unspecified"))
      (node (ref "FPC3") (pin "10") (pinfunction "10_10") (pintype "unspecified"))
      (node (ref "FPC3") (pin "23") (pinfunction "23_23") (pintype "unspecified"))
      (node (ref "FPC3") (pin "25") (pinfunction "25_25") (pintype "unspecified"))
      (node (ref "FPC3") (pin "26") (pinfunction "26_26") (pintype "unspecified"))
      (node (ref "HUM") (pin "5") (pinfunction "GND_5") (pintype "unspecified"))
      (node (ref "IND") (pin "1") (pinfunction "K_1") (pintype "unspecified"))
      (node (ref "LS") (pin "3") (pinfunction "GND_3") (pintype "unspecified"))
      (node (ref "PB1") (pin "1") (pinfunction "1_1") (pintype "unspecified"))
      (node (ref "PB1") (pin "3") (pinfunction "3_3") (pintype "unspecified"))
      (node (ref "PB1") (pin "4") (pinfunction "4_4") (pintype "unspecified"))
      (node (ref "PB2") (pin "2") (pinfunction "2_2") (pintype "unspecified"))
      (node (ref "PB2") (pin "3") (pinfunction "3_3") (pintype "unspecified"))
      (node (ref "PB2") (pin "4") (pinfunction "4_4") (pintype "unspecified"))
      (node (ref "PWR") (pin "1") (pinfunction "K_1") (pintype "unspecified"))
      (node (ref "Q4") (pin "2") (pinfunction "E_2") (pintype "unspecified"))
      (node (ref "Q5") (pin "2") (pinfunction "E_2") (pintype "unspecified"))
      (node (ref "R18") (pin "1") (pinfunction "1_1") (pintype "unspecified"))
      (node (ref "R21") (pin "2") (pinfunction "2_2") (pintype "unspecified"))
      (node (ref "R22") (pin "2") (pinfunction "2_2") (pintype "input"))
      (node (ref "R24") (pin "2") (pinfunction "2_2") (pintype "unspecified"))
      (node (ref "R25") (pin "1") (pinfunction "1_1") (pintype "unspecified"))
      (node (ref "R26") (pin "1") (pinfunction "1_1") (pintype "unspecified"))
      (node (ref "R27") (pin "1") (pinfunction "1_1") (pintype "unspecified"))
      (node (ref "R3") (pin "1") (pinfunction "1_1") (pintype "input"))
      (node (ref "R32") (pin "2") (pinfunction "2_2") (pintype "input"))
      (node (ref "R40") (pin "1") (pinfunction "1_1") (pintype "input"))
      (node (ref "R42") (pin "2") (pinfunction "2_2") (pintype "input"))
      (node (ref "R5") (pin "2") (pinfunction "2_2") (pintype "input"))
      (node (ref "RGB1") (pin "2") (pinfunction "GND_2") (pintype "unspecified"))
      (node (ref "RGB2") (pin "2") (pinfunction "GND_2") (pintype "unspecified"))
      (node (ref "RST") (pin "2") (pinfunction "2_2") (pintype "unspecified"))
      (node (ref "SP1") (pin "3") (pinfunction "3_3") (pintype "unspecified"))
      (node (ref "SP1") (pin "4") (pinfunction "4_4") (pintype "unspecified"))
      (node (ref "SW1") (pin "3") (pinfunction "3_3") (pintype "input"))
      (node (ref "SW1") (pin "4") (pinfunction "4_4") (pintype "input"))
      (node (ref "SW2") (pin "3") (pinfunction "3_3") (pintype "input"))
      (node (ref "SW2") (pin "4") (pinfunction "4_4") (pintype "input"))
      (node (ref "SW3") (pin "3") (pinfunction "3_3") (pintype "input"))
      (node (ref "SW3") (pin "4") (pinfunction "4_4") (pintype "input"))
      (node (ref "TF1") (pin "10") (pinfunction "GND_10") (pintype "unspecified"))
      (node (ref "TF1") (pin "11") (pinfunction "GND_11") (pintype "unspecified"))
      (node (ref "TF1") (pin "12") (pinfunction "GND_12") (pintype "unspecified"))
      (node (ref "TF1") (pin "13") (pinfunction "GND_13") (pintype "unspecified"))
      (node (ref "TF1") (pin "6") (pinfunction "VSS_6") (pintype "unspecified"))
      (node (ref "U1") (pin "1") (pinfunction "GND_1") (pintype "unspecified"))
      (node (ref "U1") (pin "40") (pinfunction "GND_40") (pintype "unspecified"))
      (node (ref "U1") (pin "41") (pinfunction "GND_41") (pintype "unspecified"))
      (node (ref "U10") (pin "13") (pinfunction "A1_13") (pintype "unspecified"))
      (node (ref "U10") (pin "14") (pinfunction "A0_14") (pintype "unspecified"))
      (node (ref "U10") (pin "6") (pinfunction "GND_6") (pintype "unspecified"))
      (node (ref "U11") (pin "2") (pinfunction "GND_2") (pintype "unspecified"))
      (node (ref "U12") (pin "2") (pinfunction "GND_2") (pintype "unspecified"))
      (node (ref "U13") (pin "7") (pinfunction "GND_7") (pintype "unspecified"))
      (node (ref "U13") (pin "9") (pinfunction "EP_9") (pintype "unspecified"))
      (node (ref "U14") (pin "13") (pinfunction "GNDA_13") (pintype "unspecified"))
      (node (ref "U14") (pin "21") (pinfunction "EP_21") (pintype "unspecified"))
      (node (ref "U14") (pin "4") (pinfunction "GNDD_4") (pintype "unspecified"))
      (node (ref "U14") (pin "8") (pinfunction "AD1_8") (pintype "unspecified"))
      (node (ref "U17") (pin "2") (pinfunction "VSS_2") (pintype "unspecified"))
      (node (ref "U18") (pin "1") (pinfunction "ISO14443LB_1") (pintype "unspecified"))
      (node (ref "U18") (pin "17") (pinfunction "ISO14443LA_17") (pintype "unspecified"))
      (node (ref "U18") (pin "19") (pinfunction "VSS_19") (pintype "unspecified"))
      (node (ref "U18") (pin "21") (pinfunction "EP_21") (pintype "unspecified"))
      (node (ref "U2") (pin "4") (pinfunction "GND_4") (pintype "unspecified"))
      (node (ref "U3") (pin "2") (pinfunction "GND_2") (pintype "input"))
      (node (ref "U4") (pin "1") (pinfunction "CSP_1") (pintype "unspecified"))
      (node (ref "U4") (pin "12") (pinfunction "TEST_12") (pintype "unspecified"))
      (node (ref "U4") (pin "14") (pinfunction "GND_14") (pintype "unspecified"))
      (node (ref "U4") (pin "3") (pinfunction "PGND_3") (pintype "unspecified"))
      (node (ref "U4") (pin "6") (pinfunction "OLIM_6") (pintype "unspecified"))
      (node (ref "U5") (pin "4") (pinfunction "NC_4") (pintype "unspecified"))
      (node (ref "U5") (pin "8") (pinfunction "GNDIO_8") (pintype "unspecified"))
      (node (ref "U5") (pin "9") (pinfunction "GND_9") (pintype "unspecified"))
      (node (ref "U8") (pin "1") (pinfunction "GND_1") (pintype "unspecified"))
      (node (ref "U8") (pin "11") (pinfunction "EP_11") (pintype "unspecified"))
      (node (ref "U8") (pin "2") (pinfunction "GND_2") (pintype "unspecified"))
      (node (ref "U8") (pin "4") (pinfunction "GND_4") (pintype "unspecified"))
      (node (ref "U8") (pin "5") (pinfunction "GND_5") (pintype "unspecified"))
      (node (ref "U8") (pin "6") (pinfunction "GND_6") (pintype "unspecified"))
      (node (ref "U8") (pin "7") (pinfunction "GND_7") (pintype "unspecified"))
      (node (ref "U9") (pin "18") (pinfunction "A0_18") (pintype "unspecified"))
      (node (ref "U9") (pin "23") (pinfunction "A1_23") (pintype "unspecified"))
      (node (ref "U9") (pin "24") (pinfunction "A2_24") (pintype "unspecified"))
      (node (ref "U9") (pin "25") (pinfunction "EP_25") (pintype "unspecified"))
      (node (ref "U9") (pin "9") (pinfunction "GND_9") (pintype "unspecified"))
      (node (ref "USB1") (pin "0") (pinfunction "SH_0") (pintype "unspecified"))
      (node (ref "USB1") (pin "1") (pinfunction "SH_1") (pintype "unspecified"))
      (node (ref "USB1") (pin "2") (pinfunction "SH_2") (pintype "unspecified"))
      (node (ref "USB1") (pin "3") (pinfunction "SH_3") (pintype "unspecified"))
      (node (ref "USB1") (pin "A1") (pinfunction "GND_A1") (pintype "unspecified"))
      (node (ref "USB1") (pin "A12") (pinfunction "GND_A12") (pintype "unspecified"))
      (node (ref "USB1") (pin "B1") (pinfunction "GND_B1") (pintype "unspecified"))
      (node (ref "USB1") (pin "B12") (pinfunction "GND_B12") (pintype "unspecified"))
    )
    (net (code "26") (name "I2S_LRCK") (class "Default")
      (node (ref "U1") (pin "31") (pinfunction "IO38_31") (pintype "unspecified"))
      (node (ref "U13") (pin "2") (pinfunction "LRCLK_2") (pintype "unspecified"))
      (node (ref "U14") (pin "7") (pinfunction "LRCK_7") (pintype "unspecified"))
    )
    (net (code "27") (name "I2S_MCLK") (class "Default")
      (node (ref "U1") (pin "15") (pinfunction "IO3_15") (pintype "unspecified"))
      (node (ref "U14") (pin "20") (pinfunction "MCLK_20") (pintype "unspecified"))
    )
    (net (code "28") (name "I2S_SDI") (class "Default")
      (node (ref "U1") (pin "26") (pinfunction "IO45_26") (pintype "unspecified"))
      (node (ref "U13") (pin "4") (pinfunction "SDATA_4") (pintype "unspecified"))
    )
    (net (code "29") (name "I2S_SDO") (class "Default")
      (node (ref "R21") (pin "1") (pinfunction "1_1") (pintype "unspecified"))
      (node (ref "U1") (pin "32") (pinfunction "IO39_32") (pintype "unspecified"))
      (node (ref "U14") (pin "3") (pinfunction "SDOUT/AD2_3") (pintype "unspecified"))
    )
    (net (code "30") (name "LCD_BLK") (class "Default")
      (node (ref "R19") (pin "2") (pinfunction "2_2") (pintype "input"))
      (node (ref "U9") (pin "1") (pinfunction "P00_1") (pintype "unspecified"))
    )
    (net (code "31") (name "LCD_CS") (class "Default")
      (node (ref "FPC1") (pin "14") (pinfunction "14_14") (pintype "unspecified"))
      (node (ref "U1") (pin "22") (pinfunction "IO14_22") (pintype "unspecified"))
    )
    (net (code "32") (name "LCD_DC") (class "Default")
      (node (ref "FPC1") (pin "15") (pinfunction "15_15") (pintype "unspecified"))
      (node (ref "U1") (pin "21") (pinfunction "IO13_21") (pintype "unspecified"))
    )
    (net (code "33") (name "LCD_MOSI") (class "Default")
      (node (ref "FPC1") (pin "13") (pinfunction "13_13") (pintype "unspecified"))
      (node (ref "U1") (pin "23") (pinfunction "IO21_23") (pintype "unspecified"))
    )
    (net (code "34") (name "LCD_SCLK") (class "Default")
      (node (ref "FPC1") (pin "16") (pinfunction "16_16") (pintype "unspecified"))
      (node (ref "U1") (pin "20") (pinfunction "IO12_20") (pintype "unspecified"))
    )
    (net (code "35") (name "MISO3") (class "Default")
      (node (ref "TF1") (pin "7") (pinfunction "DAT0_7") (pintype "unspecified"))
      (node (ref "U1") (pin "34") (pinfunction "IO41_34") (pintype "unspecified"))
      (node (ref "U2") (pin "2") (pinfunction "SO_2") (pintype "unspecified"))
    )
    (net (code "36") (name "MOSI3") (class "Default")
      (node (ref "TF1") (pin "3") (pinfunction "CMD_3") (pintype "unspecified"))
      (node (ref "U1") (pin "35") (pinfunction "IO42_35") (pintype "unspecified"))
      (node (ref "U2") (pin "5") (pinfunction "SI_5") (pintype "unspecified"))
    )
    (net (code "37") (name "Net-(C25-Pad2)") (class "Default")
      (node (ref "C25") (pin "2") (pinfunction "2_2") (pintype "unspecified"))
      (node (ref "FPC1") (pin "17") (pinfunction "17_17") (pintype "unspecified"))
      (node (ref "R20") (pin "1") (pinfunction "1_1") (pintype "unspecified"))
    )
    (net (code "38") (name "Net-(FPC1-Pad5)") (class "Default")
      (node (ref "FPC1") (pin "5") (pinfunction "5_5") (pintype "unspecified"))
      (node (ref "FPC1") (pin "6") (pinfunction "6_6") (pintype "unspecified"))
      (node (ref "FPC1") (pin "7") (pinfunction "7_7") (pintype "unspecified"))
      (node (ref "FPC1") (pin "8") (pinfunction "8_8") (pintype "unspecified"))
      (node (ref "R17") (pin "2") (pinfunction "2_2") (pintype "input"))
    )
    (net (code "39") (name "Net-(FPC3-Pad17)") (class "Default")
      (node (ref "FPC3") (pin "17") (pinfunction "17_17") (pintype "unspecified"))
      (node (ref "R32") (pin "1") (pinfunction "1_1") (pintype "input"))
    )
    (net (code "40") (name "Net-(IND-A)") (class "Default")
      (node (ref "IND") (pin "2") (pinfunction "A_2") (pintype "unspecified"))
      (node (ref "R16") (pin "2") (pinfunction "2_2") (pintype "input"))
    )
    (net (code "41") (name "Net-(LED1-A)") (class "Default")
      (node (ref "LED1") (pin "2") (pinfunction "A_2") (pintype "unspecified"))
      (node (ref "R2") (pin "2") (pinfunction "2_2") (pintype "input"))
    )
    (net (code "42") (name "Net-(LED1-K)") (class "Default")
      (node (ref "LED1") (pin "1") (pinfunction "K_1") (pintype "unspecified"))
      (node (ref "U17") (pin "1") (pinfunction "STAT_1") (pintype "unspecified"))
    )
    (net (code "43") (name "Net-(MIC1-OUT)") (class "Default")
      (node (ref "C27") (pin "2") (pinfunction "2_2") (pintype "input"))
      (node (ref "C6") (pin "2") (pinfunction "2_2") (pintype "input"))
      (node (ref "MIC1") (pin "2") (pinfunction "OUT_2") (pintype "unspecified"))
    )
    (net (code "44") (name "Net-(MIC2-OUT)") (class "Default")
      (node (ref "C38") (pin "2") (pinfunction "2_2") (pintype "input"))
      (node (ref "C40") (pin "2") (pinfunction "2_2") (pintype "input"))
      (node (ref "MIC2") (pin "2") (pinfunction "OUT_2") (pintype "unspecified"))
    )
    (net (code "45") (name "Net-(PWR-A)") (class "Default")
      (node (ref "PWR") (pin "2") (pinfunction "A_2") (pintype "unspecified"))
      (node (ref "R15") (pin "1") (pinfunction "1_1") (pintype "input"))
    )
    (net (code "46") (name "Net-(Q2-G)") (class "Default")
      (node (ref "D6") (pin "2") (pinfunction "2_2") (pintype "unspecified"))
      (node (ref "Q2") (pin "1") (pinfunction "G_1") (pintype "unspecified"))
      (node (ref "Q3") (pin "3") (pinfunction "C2_3") (pintype "unspecified"))
      (node (ref "R26") (pin "2") (pinfunction "2_2") (pintype "unspecified"))
    )
    (net (code "47") (name "Net-(Q3-B1)") (class "Default")
      (node (ref "Q3") (pin "2") (pinfunction "B1_2") (pintype "unspecified"))
      (node (ref "Q3") (pin "5") (pinfunction "B2_5") (pintype "unspecified"))
      (node (ref "Q3") (pin "6") (pinfunction "C1_6") (pintype "unspecified"))
      (node (ref "R25") (pin "2") (pinfunction "2_2") (pintype "unspecified"))
    )
    (net (code "48") (name "Net-(Q4-B)") (class "Default")
      (node (ref "Q4") (pin "1") (pinfunction "B_1") (pintype "unspecified"))
      (node (ref "R18") (pin "2") (pinfunction "2_2") (pintype "unspecified"))
      (node (ref "R19") (pin "1") (pinfunction "1_1") (pintype "input"))
    )
    (net (code "49") (name "Net-(Q4-C)") (class "Default")
      (node (ref "Q4") (pin "3") (pinfunction "C_3") (pintype "unspecified"))
      (node (ref "R17") (pin "1") (pinfunction "1_1") (pintype "input"))
    )
    (net (code "50") (name "Net-(Q5-B)") (class "Default")
      (node (ref "Q5") (pin "1") (pinfunction "B_1") (pintype "unspecified"))
      (node (ref "R27") (pin "2") (pinfunction "2_2") (pintype "unspecified"))
      (node (ref "R28") (pin "1") (pinfunction "1_1") (pintype "unspecified"))
    )
    (net (code "51") (name "Net-(Q5-C)") (class "Default")
      (node (ref "Q5") (pin "3") (pinfunction "C_3") (pintype "unspecified"))
      (node (ref "R29") (pin "1") (pinfunction "1_1") (pintype "unspecified"))
      (node (ref "U2") (pin "1") (pinfunction "CS#_1") (pintype "unspecified"))
    )
    (net (code "52") (name "Net-(R41-Pad2)") (class "Default")
      (node (ref "R41") (pin "2") (pinfunction "2_2") (pintype "input"))
      (node (ref "R42") (pin "1") (pinfunction "1_1") (pintype "input"))
    )
    (net (code "53") (name "Net-(RGB1-DOUT)") (class "Default")
      (node (ref "RGB1") (pin "1") (pinfunction "DOUT_1") (pintype "unspecified"))
      (node (ref "RGB2") (pin "3") (pinfunction "DIN_3") (pintype "unspecified"))
    )
    (net (code "54") (name "Net-(U2-HOLD#)") (class "Default")
      (node (ref "R31") (pin "2") (pinfunction "2_2") (pintype "unspecified"))
      (node (ref "U2") (pin "7") (pinfunction "HOLD#_7") (pintype "unspecified"))
    )
    (net (code "55") (name "Net-(U4-BST1)") (class "Default")
      (node (ref "C57") (pin "1") (pinfunction "1_1") (pintype "unspecified"))
      (node (ref "U4") (pin "8") (pinfunction "BST1_8") (pintype "unspecified"))
    )
    (net (code "56") (name "Net-(U4-BST2)") (class "Default")
      (node (ref "C56") (pin "1") (pinfunction "1_1") (pintype "unspecified"))
      (node (ref "U4") (pin "11") (pinfunction "BST2_11") (pintype "unspecified"))
    )
    (net (code "57") (name "Net-(U4-FB)") (class "Default")
      (node (ref "R23") (pin "1") (pinfunction "1_1") (pintype "input"))
      (node (ref "R24") (pin "1") (pinfunction "1_1") (pintype "unspecified"))
      (node (ref "U4") (pin "5") (pinfunction "FB_5") (pintype "unspecified"))
    )
    (net (code "58") (name "Net-(U4-SW1)") (class "Default")
      (node (ref "C57") (pin "2") (pinfunction "2_2") (pintype "unspecified"))
      (node (ref "L1") (pin "2") (pinfunction "2_2") (pintype "unspecified"))
      (node (ref "U4") (pin "9") (pinfunction "SW1_9") (pintype "unspecified"))
    )
    (net (code "59") (name "Net-(U4-SW2)") (class "Default")
      (node (ref "C56") (pin "2") (pinfunction "2_2") (pintype "unspecified"))
      (node (ref "L1") (pin "1") (pinfunction "1_1") (pintype "unspecified"))
      (node (ref "U4") (pin "10") (pinfunction "SW2_10") (pintype "unspecified"))
    )
    (net (code "60") (name "Net-(U13-VON)") (class "Default")
      (node (ref "SP1") (pin "1") (pinfunction "1_1") (pintype "unspecified"))
      (node (ref "U13") (pin "5") (pinfunction "VON_5") (pintype "unspecified"))
    )
    (net (code "61") (name "Net-(U13-VOP)") (class "Default")
      (node (ref "SP1") (pin "2") (pinfunction "2_2") (pintype "unspecified"))
      (node (ref "U13") (pin "8") (pinfunction "VOP_8") (pintype "unspecified"))
    )
    (net (code "62") (name "Net-(U14-AINLN)") (class "Default")
      (node (ref "C28") (pin "1") (pinfunction "1_1") (pintype "input"))
      (node (ref "U14") (pin "10") (pinfunction "AINLN_10") (pintype "unspecified"))
    )
    (net (code "63") (name "Net-(U14-AINLP)") (class "Default")
      (node (ref "C27") (pin "1") (pinfunction "1_1") (pintype "input"))
      (node (ref "U14") (pin "9") (pinfunction "AINLP_9") (pintype "unspecified"))
    )
    (net (code "64") (name "Net-(U14-AINRN)") (class "Default")
      (node (ref "C39") (pin "1") (pinfunction "1_1") (pintype "input"))
      (node (ref "U14") (pin "15") (pinfunction "AINRN_15") (pintype "unspecified"))
    )
    (net (code "65") (name "Net-(U14-AINRP)") (class "Default")
      (node (ref "C38") (pin "1") (pinfunction "1_1") (pintype "input"))
      (node (ref "U14") (pin "16") (pinfunction "AINRP_16") (pintype "unspecified"))
    )
    (net (code "66") (name "Net-(U14-REFP)") (class "Default")
      (node (ref "C43") (pin "2") (pinfunction "2_2") (pintype "input"))
      (node (ref "U14") (pin "14") (pinfunction "REFP_14") (pintype "unspecified"))
    )
    (net (code "67") (name "Net-(U14-REFQ)") (class "Default")
      (node (ref "C42") (pin "2") (pinfunction "2_2") (pintype "input"))
      (node (ref "U14") (pin "11") (pinfunction "REFQ_11") (pintype "unspecified"))
    )
    (net (code "68") (name "Net-(U17-PROG)") (class "Default")
      (node (ref "R40") (pin "2") (pinfunction "2_2") (pintype "input"))
      (node (ref "R41") (pin "1") (pinfunction "1_1") (pintype "input"))
      (node (ref "U17") (pin "5") (pinfunction "PROG_5") (pintype "unspecified"))
    )
    (net (code "69") (name "Net-(U18-ENA)") (class "Default")
      (node (ref "R43") (pin "1") (pinfunction "1_1") (pintype "unspecified"))
      (node (ref "U18") (pin "11") (pinfunction "ENA_11") (pintype "unspecified"))
    )
    (net (code "70") (name "Net-(U18-VCC)") (class "Default")
      (node (ref "C67") (pin "2") (pinfunction "2_2") (pintype "unspecified"))
      (node (ref "U18") (pin "15") (pinfunction "VOUT_15") (pintype "unspecified"))
      (node (ref "U18") (pin "18") (pinfunction "VCC_18") (pintype "unspecified"))
    )
    (net (code "71") (name "P0") (class "Default")
      (node (ref "C_P0") (pin "3") (pinfunction "3_3") (pintype "unspecified"))
      (node (ref "U1") (pin "39") (pinfunction "IO1_39") (pintype "unspecified"))
    )
    (net (code "72") (name "P1") (class "Default")
      (node (ref "C_P1-3") (pin "3") (pinfunction "3_3") (pintype "unspecified"))
      (node (ref "U9") (pin "8") (pinfunction "P07_8") (pintype "unspecified"))
    )
    (net (code "73") (name "P2") (class "Default")
      (node (ref "C_P1-3") (pin "4") (pinfunction "4_4") (pintype "unspecified"))
      (node (ref "U9") (pin "16") (pinfunction "P16_16") (pintype "unspecified"))
    )
    (net (code "74") (name "P3") (class "Default")
      (node (ref "C_P1-3") (pin "5") (pinfunction "5_5") (pintype "unspecified"))
      (node (ref "U9") (pin "15") (pinfunction "P15_15") (pintype "unspecified"))
    )
    (net (code "75") (name "P4") (class "Default")
      (node (ref "C_P4-7") (pin "3") (pinfunction "3_3") (pintype "unspecified"))
      (node (ref "U9") (pin "14") (pinfunction "P14_14") (pintype "unspecified"))
    )
    (net (code "76") (name "P5") (class "Default")
      (node (ref "C_P4-7") (pin "4") (pinfunction "4_4") (pintype "unspecified"))
      (node (ref "U9") (pin "13") (pinfunction "P13_13") (pintype "unspecified"))
    )
    (net (code "77") (name "P6") (class "Default")
      (node (ref "C_P4-7") (pin "5") (pinfunction "5_5") (pintype "unspecified"))
      (node (ref "U9") (pin "10") (pinfunction "P10_10") (pintype "unspecified"))
    )
    (net (code "78") (name "P7") (class "Default")
      (node (ref "C_P4-7") (pin "6") (pinfunction "6_6") (pintype "unspecified"))
      (node (ref "R39") (pin "1") (pinfunction "1_1") (pintype "unspecified"))
      (node (ref "SW3") (pin "1") (pinfunction "1_1") (pintype "input"))
      (node (ref "SW3") (pin "2") (pinfunction "2_2") (pintype "input"))
      (node (ref "U9") (pin "11") (pinfunction "P11_11") (pintype "unspecified"))
    )
    (net (code "79") (name "P8") (class "Default")
      (node (ref "R37") (pin "1") (pinfunction "1_1") (pintype "unspecified"))
      (node (ref "SW1") (pin "1") (pinfunction "1_1") (pintype "input"))
      (node (ref "SW1") (pin "2") (pinfunction "2_2") (pintype "input"))
      (node (ref "U9") (pin "12") (pinfunction "P12_12") (pintype "unspecified"))
    )
    (net (code "80") (name "P9") (class "Default")
      (node (ref "R38") (pin "1") (pinfunction "1_1") (pintype "unspecified"))
      (node (ref "SW2") (pin "1") (pinfunction "1_1") (pintype "input"))
      (node (ref "SW2") (pin "2") (pinfunction "2_2") (pintype "input"))
      (node (ref "U9") (pin "5") (pinfunction "P04_5") (pintype "unspecified"))
    )
    (net (code "81") (name "P10") (class "Default")
      (node (ref "C21") (pin "2") (pinfunction "2_2") (pintype "unspecified"))
      (node (ref "PB1") (pin "2") (pinfunction "2_2") (pintype "unspecified"))
      (node (ref "R7") (pin "1") (pinfunction "1_1") (pintype "unspecified"))
      (node (ref "U9") (pin "6") (pinfunction "P05_6") (pintype "unspecified"))
    )
    (net (code "82") (name "P11") (class "Default")
      (node (ref "C20") (pin "2") (pinfunction "2_2") (pintype "unspecified"))
      (node (ref "PB2") (pin "1") (pinfunction "1_1") (pintype "unspecified"))
      (node (ref "R6") (pin "1") (pinfunction "1_1") (pintype "unspecified"))
      (node (ref "U9") (pin "7") (pinfunction "P06_7") (pintype "unspecified"))
    )
    (net (code "83") (name "RGB") (class "Default")
      (node (ref "RGB1") (pin "3") (pinfunction "DIN_3") (pintype "unspecified"))
      (node (ref "U1") (pin "16") (pinfunction "IO46_16") (pintype "unspecified"))
    )
    (net (code "84") (name "RST") (class "Default")
      (node (ref "C3") (pin "2") (pinfunction "2_2") (pintype "input"))
      (node (ref "R1") (pin "1") (pinfunction "1_1") (pintype "unspecified"))
      (node (ref "RST") (pin "1") (pinfunction "1_1") (pintype "unspecified"))
      (node (ref "U1") (pin "3") (pinfunction "EN_3") (pintype "unspecified"))
    )
    (net (code "85") (name "SCL") (class "Default")
      (node (ref "C_I2C") (pin "3") (pinfunction "3_3") (pintype "unspecified"))
      (node (ref "FPC2") (pin "3") (pinfunction "3_3") (pintype "unspecified"))
      (node (ref "FPC3") (pin "20") (pinfunction "20_20") (pintype "unspecified"))
      (node (ref "HUM") (pin "3") (pinfunction "SCL_3") (pintype "unspecified"))
      (node (ref "LS") (pin "4") (pinfunction "SCL_4") (pintype "unspecified"))
      (node (ref "R13") (pin "1") (pinfunction "1_1") (pintype "unspecified"))
      (node (ref "R34") (pin "1") (pinfunction "1_1") (pintype "unspecified"))
      (node (ref "R36") (pin "1") (pinfunction "1_1") (pintype "unspecified"))
      (node (ref "U1") (pin "25") (pinfunction "IO48_25") (pintype "unspecified"))
      (node (ref "U10") (pin "12") (pinfunction "SCL_12") (pintype "unspecified"))
      (node (ref "U14") (pin "19") (pinfunction "CCLK_19") (pintype "unspecified"))
      (node (ref "U18") (pin "10") (pinfunction "l2C_SCL_10") (pintype "unspecified"))
      (node (ref "U5") (pin "12") (pinfunction "SCx_12") (pintype "unspecified"))
      (node (ref "U8") (pin "8") (pinfunction "SCL_8") (pintype "unspecified"))
      (node (ref "U9") (pin "19") (pinfunction "SCL_19") (pintype "unspecified"))
    )
    (net (code "86") (name "SCLK3") (class "Default")
      (node (ref "TF1") (pin "5") (pinfunction "CLK_5") (pintype "unspecified"))
      (node (ref "U1") (pin "36") (pinfunction "RXD0_36") (pintype "unspecified"))
      (node (ref "U2") (pin "6") (pinfunction "SCLK_6") (pintype "unspecified"))
    )
    (net (code "87") (name "SDA") (class "Default")
      (node (ref "C_I2C") (pin "4") (pinfunction "4_4") (pintype "unspecified"))
      (node (ref "FPC2") (pin "2") (pinfunction "2_2") (pintype "unspecified"))
      (node (ref "FPC3") (pin "22") (pinfunction "22_22") (pintype "unspecified"))
      (node (ref "HUM") (pin "4") (pinfunction "SDA_4") (pintype "unspecified"))
      (node (ref "LS") (pin "6") (pinfunction "SDA_6") (pintype "unspecified"))
      (node (ref "R12") (pin "2") (pinfunction "2_2") (pintype "unspecified"))
      (node (ref "R33") (pin "2") (pinfunction "2_2") (pintype "unspecified"))
      (node (ref "R35") (pin "2") (pinfunction "2_2") (pintype "unspecified"))
      (node (ref "U1") (pin "24") (pinfunction "IO47_24") (pintype "unspecified"))
      (node (ref "U10") (pin "11") (pinfunction "SDA_11") (pintype "unspecified"))
      (node (ref "U14") (pin "18") (pinfunction "CDATA_18") (pintype "unspecified"))
      (node (ref "U18") (pin "9") (pinfunction "l2C_SDA_9") (pintype "unspecified"))
      (node (ref "U5") (pin "2") (pinfunction "SDx_2") (pintype "unspecified"))
      (node (ref "U8") (pin "3") (pinfunction "SDA_3") (pintype "unspecified"))
      (node (ref "U9") (pin "20") (pinfunction "DA_20") (pintype "unspecified"))
    )
    (net (code "88") (name "SE_RST") (class "Default")
      (node (ref "U18") (pin "14") (pinfunction "ISO7816RST_N_14") (pintype "unspecified"))
      (node (ref "U8") (pin "9") (pinfunction "RST_9") (pintype "unspecified"))
      (node (ref "U9") (pin "4") (pinfunction "P03_4") (pintype "unspecified"))
    )
    (net (code "89") (name "TS_INT") (class "Default")
      (node (ref "FPC2") (pin "4") (pinfunction "4_4") (pintype "unspecified"))
      (node (ref "U1") (pin "38") (pinfunction "IO2_38") (pintype "unspecified"))
      (node (ref "U10") (pin "10") (pinfunction "PENIRQ_10") (pintype "unspecified"))
    )
    (net (code "90") (name "TS_RST") (class "Default")
      (node (ref "FPC2") (pin "5") (pinfunction "5_5") (pintype "unspecified"))
      (node (ref "U9") (pin "2") (pinfunction "P01_2") (pintype "unspecified"))
    )
    (net (code "91") (name "U_LED") (class "Default")
      (node (ref "R16") (pin "1") (pinfunction "1_1") (pintype "input"))
      (node (ref "U9") (pin "17") (pinfunction "P17_17") (pintype "unspecified"))
    )
    (net (code "92") (name "VBAT") (class "Default")
      (node (ref "BATT") (pin "2") (pinfunction "2_2") (pintype "unspecified"))
      (node (ref "C66") (pin "2") (pinfunction "2_2") (pintype "input"))
      (node (ref "D5") (pin "2") (pinfunction "2_2") (pintype "unspecified"))
      (node (ref "Q2") (pin "3") (pinfunction "D_3") (pintype "unspecified"))
      (node (ref "Q3") (pin "1") (pinfunction "E1_1") (pintype "unspecified"))
      (node (ref "U17") (pin "3") (pinfunction "VBAT_3") (pintype "unspecified"))
    )
    (net (code "93") (name "VBUS") (class "Default")
      (node (ref "D2") (pin "2") (pinfunction "A_2") (pintype "unspecified"))
      (node (ref "R2") (pin "1") (pinfunction "1_1") (pintype "input"))
      (node (ref "U17") (pin "4") (pinfunction "VDD_4") (pintype "unspecified"))
      (node (ref "USB1") (pin "A4") (pinfunction "VBUS_A4") (pintype "unspecified"))
      (node (ref "USB1") (pin "A9") (pinfunction "VBUS_A9") (pintype "unspecified"))
      (node (ref "USB1") (pin "B4") (pinfunction "VBUS_B4") (pintype "unspecified"))
      (node (ref "USB1") (pin "B9") (pinfunction "VBUS_B9") (pintype "unspecified"))
    )
    (net (code "94") (name "VCC") (class "Default")
      (node (ref "C51") (pin "2") (pinfunction "2_2") (pintype "unspecified"))
      (node (ref "C52") (pin "2") (pinfunction "2_2") (pintype "unspecified"))
      (node (ref "C58") (pin "2") (pinfunction "2_2") (pintype "unspecified"))
      (node (ref "D2") (pin "1") (pinfunction "K_1") (pintype "unspecified"))
      (node (ref "D6") (pin "1") (pinfunction "1_1") (pintype "unspecified"))
      (node (ref "Q2") (pin "2") (pinfunction "S_2") (pintype "unspecified"))
      (node (ref "Q3") (pin "4") (pinfunction "E2_4") (pintype "unspecified"))
      (node (ref "U4") (pin "2") (pinfunction "VIN_2") (pintype "unspecified"))
      (node (ref "U4") (pin "7") (pinfunction "EN_7") (pintype "unspecified"))
    )
    (net (code "95") (name "VLDO") (class "Default")
      (node (ref "C54") (pin "1") (pinfunction "1_1") (pintype "unspecified"))
      (node (ref "U4") (pin "13") (pinfunction "VCC_13") (pintype "unspecified"))
      (node (ref "U4") (pin "15") (pinfunction "CSN_15") (pintype "unspecified"))
    )
    (net (code "96") (name "X+") (class "Default")
      (node (ref "FPC1") (pin "4") (pinfunction "4_4") (pintype "unspecified"))
      (node (ref "U10") (pin "2") (pinfunction "X+_2") (pintype "unspecified"))
    )
    (net (code "97") (name "X-") (class "Default")
      (node (ref "FPC1") (pin "2") (pinfunction "2_2") (pintype "unspecified"))
      (node (ref "U10") (pin "4") (pinfunction "X-_4") (pintype "unspecified"))
    )
    (net (code "98") (name "Y+") (class "Default")
      (node (ref "FPC1") (pin "3") (pinfunction "3_3") (pintype "unspecified"))
      (node (ref "U10") (pin "3") (pinfunction "Y+_3") (pintype "unspecified"))
    )
    (net (code "99") (name "Y-") (class "Default")
      (node (ref "FPC1") (pin "1") (pinfunction "1_1") (pintype "unspecified"))
      (node (ref "U10") (pin "5") (pinfunction "Y-_5") (pintype "unspecified"))
    )
    (net (code "100") (name "unconnected-(FPC3-Pad1)") (class "Default")
      (node (ref "FPC3") (pin "1") (pinfunction "1_1") (pintype "unspecified"))
    )
    (net (code "101") (name "unconnected-(FPC3-Pad2)") (class "Default")
      (node (ref "FPC3") (pin "2") (pinfunction "2_2") (pintype "unspecified"))
    )
    (net (code "102") (name "unconnected-(FPC3-Pad24)") (class "Default")
      (node (ref "FPC3") (pin "24") (pinfunction "24_24") (pintype "unspecified"))
    )
    (net (code "103") (name "unconnected-(HUM-NC-Pad1)") (class "Default")
      (node (ref "HUM") (pin "1") (pinfunction "NC_1") (pintype "unspecified"))
    )
    (net (code "104") (name "unconnected-(HUM-NC-Pad6)") (class "Default")
      (node (ref "HUM") (pin "6") (pinfunction "NC_6") (pintype "unspecified"))
    )
    (net (code "105") (name "unconnected-(LS-INT-Pad5)") (class "Default")
      (node (ref "LS") (pin "5") (pinfunction "INT_5") (pintype "unspecified"))
    )
    (net (code "106") (name "unconnected-(LS-NC-Pad2)") (class "Default")
      (node (ref "LS") (pin "2") (pinfunction "NC_2") (pintype "unspecified"))
    )
    (net (code "107") (name "unconnected-(RGB2-DOUT-Pad1)") (class "Default")
      (node (ref "RGB2") (pin "1") (pinfunction "DOUT_1") (pintype "unspecified"))
    )
    (net (code "108") (name "unconnected-(TF1-CD-Pad9)") (class "Default")
      (node (ref "TF1") (pin "9") (pinfunction "CD_9") (pintype "unspecified"))
    )
    (net (code "109") (name "unconnected-(TF1-DAT1-Pad8)") (class "Default")
      (node (ref "TF1") (pin "8") (pinfunction "DAT1_8") (pintype "unspecified"))
    )
    (net (code "110") (name "unconnected-(TF1-DAT2-Pad1)") (class "Default")
      (node (ref "TF1") (pin "1") (pinfunction "DAT2_1") (pintype "unspecified"))
    )
    (net (code "111") (name "unconnected-(U1-IO35-Pad28)") (class "Default")
      (node (ref "U1") (pin "28") (pinfunction "IO35_28") (pintype "unspecified"))
    )
    (net (code "112") (name "unconnected-(U1-IO36-Pad29)") (class "Default")
      (node (ref "U1") (pin "29") (pinfunction "IO36_29") (pintype "unspecified"))
    )
    (net (code "113") (name "unconnected-(U1-IO37-Pad30)") (class "Default")
      (node (ref "U1") (pin "30") (pinfunction "IO37_30") (pintype "unspecified"))
    )
    (net (code "114") (name "unconnected-(U2-NC-Pad3)") (class "Default")
      (node (ref "U2") (pin "3") (pinfunction "NC_3") (pintype "unspecified"))
    )
    (net (code "115") (name "unconnected-(U3-NC-Pad5)") (class "Default")
      (node (ref "U3") (pin "5") (pinfunction "NC_5") (pintype "input"))
    )
    (net (code "116") (name "unconnected-(U5-CS-Pad10)") (class "Default")
      (node (ref "U5") (pin "10") (pinfunction "CS_10") (pintype "unspecified"))
    )
    (net (code "117") (name "unconnected-(U5-INT1-Pad5)") (class "Default")
      (node (ref "U5") (pin "5") (pinfunction "INT1_5") (pintype "unspecified"))
    )
    (net (code "118") (name "unconnected-(U5-INT2-Pad6)") (class "Default")
      (node (ref "U5") (pin "6") (pinfunction "INT2_6") (pintype "unspecified"))
    )
    (net (code "119") (name "unconnected-(U5-NC-Pad11)") (class "Default")
      (node (ref "U5") (pin "11") (pinfunction "NC_11") (pintype "unspecified"))
    )
    (net (code "120") (name "unconnected-(U5-SDO-Pad1)") (class "Default")
      (node (ref "U5") (pin "1") (pinfunction "SDO_1") (pintype "unspecified"))
    )
    (net (code "121") (name "unconnected-(U10-AUX-Pad16)") (class "Default")
      (node (ref "U10") (pin "16") (pinfunction "AUX_16") (pintype "unspecified"))
    )
    (net (code "122") (name "unconnected-(U10-NC-Pad9)") (class "Default")
      (node (ref "U10") (pin "9") (pinfunction "NC_9") (pintype "unspecified"))
    )
    (net (code "123") (name "unconnected-(U10-NC{slash}2-Pad7)") (class "Default")
      (node (ref "U10") (pin "7") (pinfunction "NC/2_7") (pintype "unspecified"))
    )
    (net (code "124") (name "unconnected-(U10-NC{slash}3-Pad15)") (class "Default")
      (node (ref "U10") (pin "15") (pinfunction "NC/3_15") (pintype "unspecified"))
    )
    (net (code "125") (name "unconnected-(U10-NC{slash}4-Pad8)") (class "Default")
      (node (ref "U10") (pin "8") (pinfunction "NC/4_8") (pintype "unspecified"))
    )
    (net (code "126") (name "unconnected-(U11-NC-Pad4)") (class "Default")
      (node (ref "U11") (pin "4") (pinfunction "NC_4") (pintype "unspecified"))
    )
    (net (code "127") (name "unconnected-(U12-NC-Pad4)") (class "Default")
      (node (ref "U12") (pin "4") (pinfunction "NC_4") (pintype "unspecified"))
    )
    (net (code "128") (name "unconnected-(U14-TDMIN-Pad2)") (class "Default")
      (node (ref "U14") (pin "2") (pinfunction "TDMIN_2") (pintype "unspecified"))
    )
    (net (code "129") (name "unconnected-(U18-ISO7816CLK-Pad13)") (class "Default")
      (node (ref "U18") (pin "13") (pinfunction "ISO7816CLK_13") (pintype "unspecified"))
    )
    (net (code "130") (name "unconnected-(U18-ISO7816IO1-Pad3)") (class "Default")
      (node (ref "U18") (pin "3") (pinfunction "ISO7816IO1_3") (pintype "unspecified"))
    )
    (net (code "131") (name "unconnected-(U18-ISO7816IO2-Pad16)") (class "Default")
      (node (ref "U18") (pin "16") (pinfunction "ISO7816IO2_16") (pintype "unspecified"))
    )
    (net (code "132") (name "unconnected-(U18-n.c.-Pad2)") (class "Default")
      (node (ref "U18") (pin "2") (pinfunction "n.c._2") (pintype "unspecified"))
    )
    (net (code "133") (name "unconnected-(U18-n.c.-Pad4)") (class "Default")
      (node (ref "U18") (pin "4") (pinfunction "n.c._4") (pintype "unspecified"))
    )
    (net (code "134") (name "unconnected-(U18-n.c.-Pad5)") (class "Default")
      (node (ref "U18") (pin "5") (pinfunction "n.c._5") (pintype "unspecified"))
    )
    (net (code "135") (name "unconnected-(U18-n.c.-Pad6)") (class "Default")
      (node (ref "U18") (pin "6") (pinfunction "n.c._6") (pintype "unspecified"))
    )
    (net (code "136") (name "unconnected-(U18-n.c.-Pad7)") (class "Default")
      (node (ref "U18") (pin "7") (pinfunction "n.c._7") (pintype "unspecified"))
    )
    (net (code "137") (name "unconnected-(U18-n.c.-Pad8)") (class "Default")
      (node (ref "U18") (pin "8") (pinfunction "n.c._8") (pintype "unspecified"))
    )
    (net (code "138") (name "unconnected-(U18-n.c.-Pad20)") (class "Default")
      (node (ref "U18") (pin "20") (pinfunction "n.c._20") (pintype "unspecified"))
    )
    (net (code "139") (name "unconnected-(USB1-SBU1-PadA8)") (class "Default")
      (node (ref "USB1") (pin "A8") (pinfunction "SBU1_A8") (pintype "unspecified"))
    )
    (net (code "140") (name "unconnected-(USB1-SBU2-PadB8)") (class "Default")
      (node (ref "USB1") (pin "B8") (pinfunction "SBU2_B8") (pintype "unspecified"))
    )
  )
)
